# Team18_V1_3.net
KiCad netlist of a schematic drawn in EAGLE
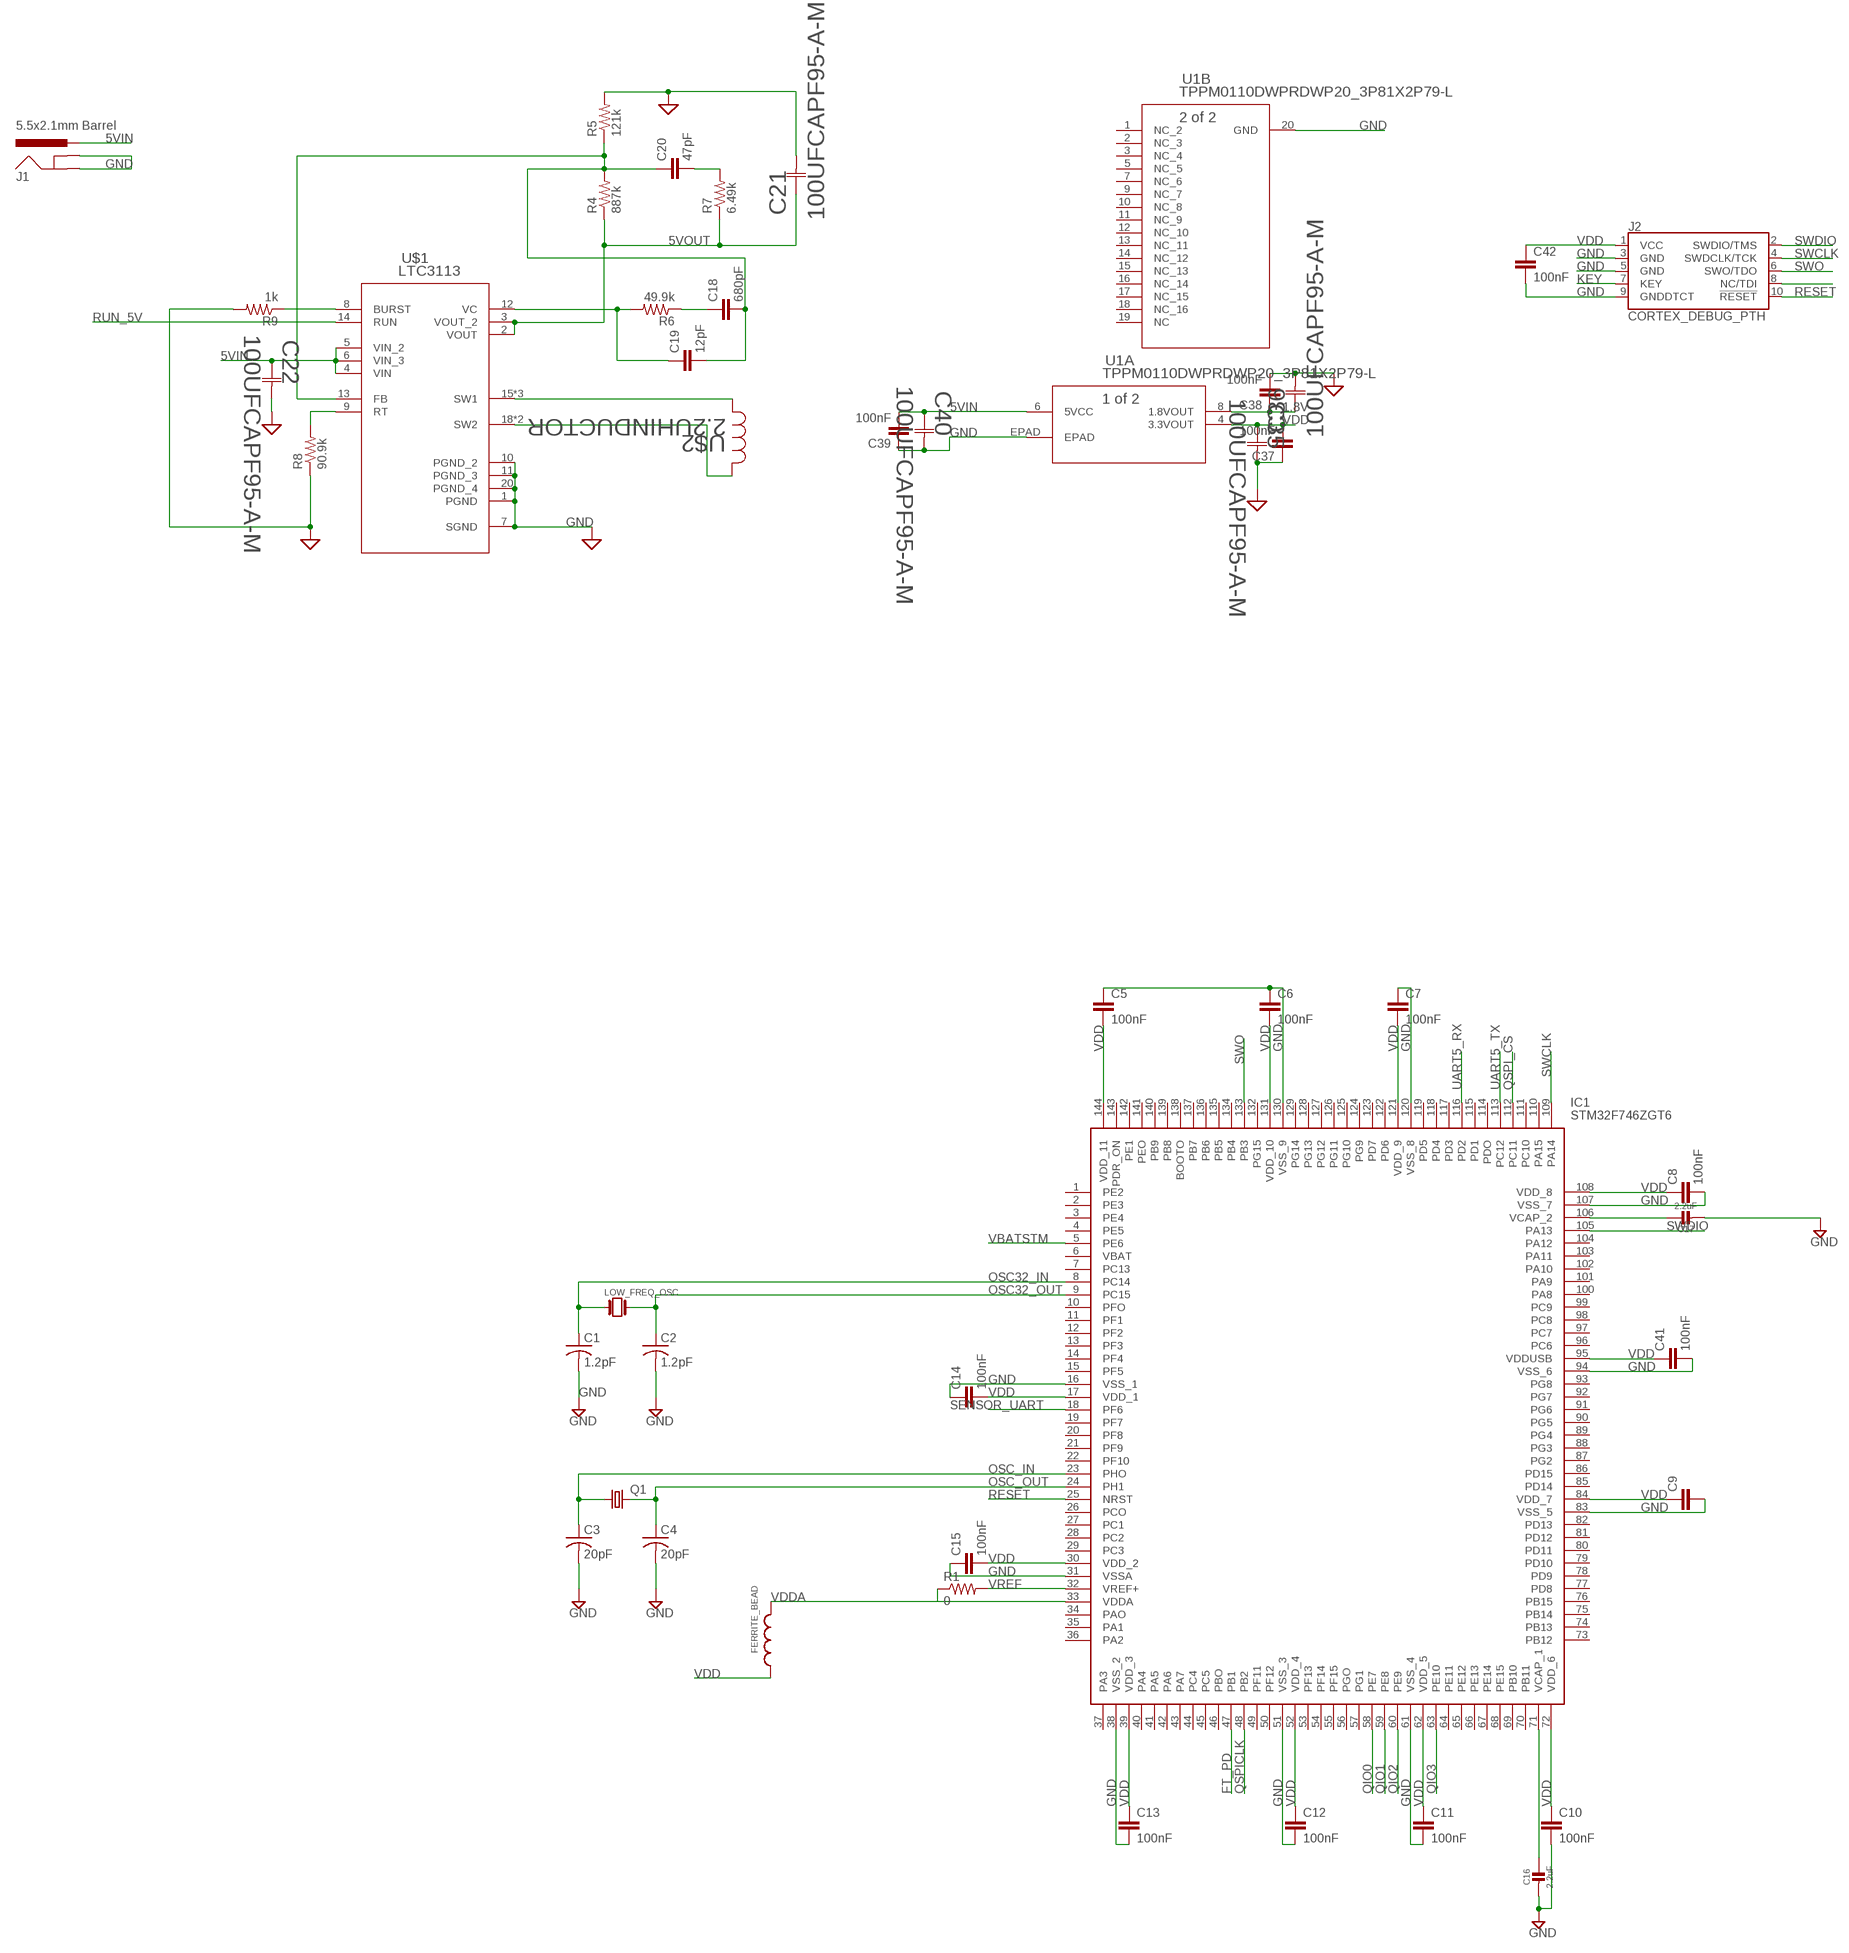
[diagram p0: schematic, sheet 1, part 1 of 2]
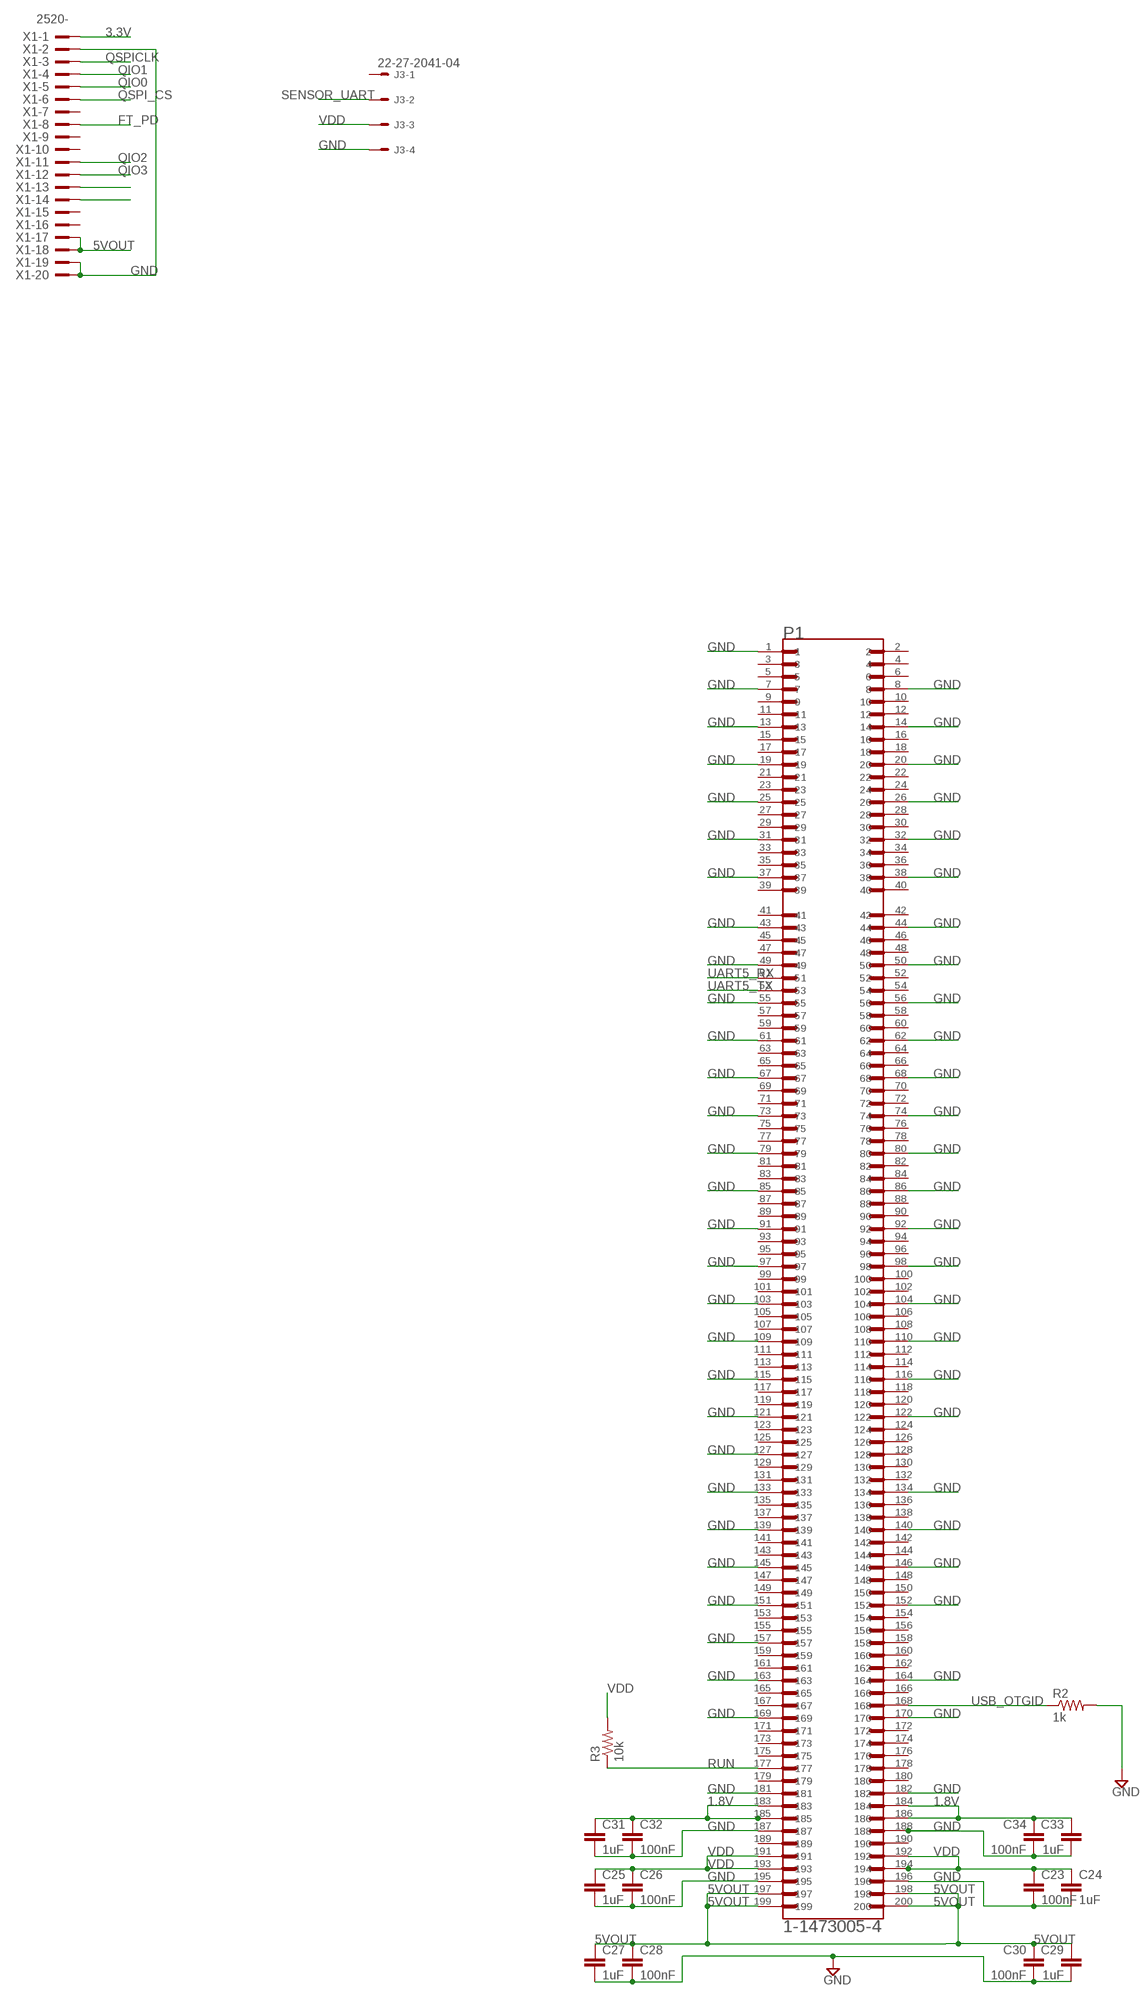
[diagram p1: schematic, sheet 1, part 2 of 2]

(export (version "E")
  (design (tool "Eeschema 10.0.6"))
  (components
    (comp (ref "C1")
      (value "1.2pF")
      (footprint "eagle-import:C0805")
      (libsource (lib "eagle-import") (part "C-USC0805"))
    )
    (comp (ref "C2")
      (value "1.2pF")
      (footprint "eagle-import:C0805")
      (libsource (lib "eagle-import") (part "C-USC0805"))
    )
    (comp (ref "C3")
      (value "20pF")
      (footprint "eagle-import:C0805")
      (libsource (lib "eagle-import") (part "C-USC0805"))
    )
    (comp (ref "C4")
      (value "20pF")
      (footprint "eagle-import:C0805")
      (libsource (lib "eagle-import") (part "C-USC0805"))
    )
    (comp (ref "C5")
      (value "100nF")
      (footprint "eagle-import:C0805")
      (libsource (lib "eagle-import") (part "C-EUC0805"))
    )
    (comp (ref "C6")
      (value "100nF")
      (footprint "eagle-import:C0805")
      (libsource (lib "eagle-import") (part "C-EUC0805"))
    )
    (comp (ref "C7")
      (value "100nF")
      (footprint "eagle-import:C0805")
      (libsource (lib "eagle-import") (part "C-EUC0805"))
    )
    (comp (ref "C8")
      (value "100nF")
      (footprint "eagle-import:C0805")
      (libsource (lib "eagle-import") (part "C-EUC0805"))
    )
    (comp (ref "C9")
      (value "C-EUC0805")
      (footprint "eagle-import:C0805")
      (libsource (lib "eagle-import") (part "C-EUC0805"))
    )
    (comp (ref "C10")
      (value "100nF")
      (footprint "eagle-import:C0805")
      (libsource (lib "eagle-import") (part "C-EUC0805"))
    )
    (comp (ref "C11")
      (value "100nF")
      (footprint "eagle-import:C0805")
      (libsource (lib "eagle-import") (part "C-EUC0805"))
    )
    (comp (ref "C12")
      (value "100nF")
      (footprint "eagle-import:C0805")
      (libsource (lib "eagle-import") (part "C-EUC0805"))
    )
    (comp (ref "C13")
      (value "100nF")
      (footprint "eagle-import:C0805")
      (libsource (lib "eagle-import") (part "C-EUC0805"))
    )
    (comp (ref "C14")
      (value "100nF")
      (footprint "eagle-import:C0805")
      (libsource (lib "eagle-import") (part "C-EUC0805"))
    )
    (comp (ref "C15")
      (value "100nF")
      (footprint "eagle-import:C0805")
      (libsource (lib "eagle-import") (part "C-EUC0805"))
    )
    (comp (ref "C16")
      (value "2.2uF")
      (footprint "eagle-import:0805-NO")
      (libsource (lib "eagle-import") (part "CAP_CERAMIC0805-NOOUTLINE"))
    )
    (comp (ref "C17")
      (value "2.2uF")
      (footprint "eagle-import:0805-NO")
      (libsource (lib "eagle-import") (part "CAP_CERAMIC0805-NOOUTLINE"))
    )
    (comp (ref "C18")
      (value "680pF")
      (footprint "eagle-import:C0805")
      (libsource (lib "eagle-import") (part "C-EUC0805"))
    )
    (comp (ref "C19")
      (value "12pF")
      (footprint "eagle-import:C0805")
      (libsource (lib "eagle-import") (part "C-EUC0805"))
    )
    (comp (ref "C20")
      (value "47pF")
      (footprint "eagle-import:C0805")
      (libsource (lib "eagle-import") (part "C-EUC0805"))
    )
    (comp (ref "C21")
      (value "100UFCAPF95-A-M")
      (footprint "eagle-import:F95-A-M")
      (fields (field (name "MANUFACTURER_PART_NUMBER") "F951A107KAAAQ2"))
      (libsource (lib "eagle-import") (part "100UFCAPF95-A-M"))
    )
    (comp (ref "C22")
      (value "100UFCAPF95-A-M")
      (footprint "eagle-import:F95-A-M")
      (fields (field (name "MANUFACTURER_PART_NUMBER") "F951A107KAAAQ2"))
      (libsource (lib "eagle-import") (part "100UFCAPF95-A-M"))
    )
    (comp (ref "C23")
      (value "100nF")
      (footprint "eagle-import:C0805")
      (libsource (lib "eagle-import") (part "C-EUC0805"))
    )
    (comp (ref "C24")
      (value "1uF")
      (footprint "eagle-import:C0805")
      (libsource (lib "eagle-import") (part "C-EUC0805"))
    )
    (comp (ref "C25")
      (value "1uF")
      (footprint "eagle-import:C0805")
      (libsource (lib "eagle-import") (part "C-EUC0805"))
    )
    (comp (ref "C26")
      (value "100nF")
      (footprint "eagle-import:C0805")
      (libsource (lib "eagle-import") (part "C-EUC0805"))
    )
    (comp (ref "C27")
      (value "1uF")
      (footprint "eagle-import:C0805")
      (libsource (lib "eagle-import") (part "C-EUC0805"))
    )
    (comp (ref "C28")
      (value "100nF")
      (footprint "eagle-import:C0805")
      (libsource (lib "eagle-import") (part "C-EUC0805"))
    )
    (comp (ref "C29")
      (value "1uF")
      (footprint "eagle-import:C0805")
      (libsource (lib "eagle-import") (part "C-EUC0805"))
    )
    (comp (ref "C30")
      (value "100nF")
      (footprint "eagle-import:C0805")
      (libsource (lib "eagle-import") (part "C-EUC0805"))
    )
    (comp (ref "C31")
      (value "1uF")
      (footprint "eagle-import:C0805")
      (libsource (lib "eagle-import") (part "C-EUC0805"))
    )
    (comp (ref "C32")
      (value "100nF")
      (footprint "eagle-import:C0805")
      (libsource (lib "eagle-import") (part "C-EUC0805"))
    )
    (comp (ref "C33")
      (value "1uF")
      (footprint "eagle-import:C0805")
      (libsource (lib "eagle-import") (part "C-EUC0805"))
    )
    (comp (ref "C34")
      (value "100nF")
      (footprint "eagle-import:C0805")
      (libsource (lib "eagle-import") (part "C-EUC0805"))
    )
    (comp (ref "C35")
      (value "100UFCAPF95-A-M")
      (footprint "eagle-import:F95-A-M")
      (fields (field (name "MANUFACTURER_PART_NUMBER") "F951A107KAAAQ2"))
      (libsource (lib "eagle-import") (part "100UFCAPF95-A-M"))
    )
    (comp (ref "C36")
      (value "100UFCAPF95-A-M")
      (footprint "eagle-import:F95-A-M")
      (fields (field (name "MANUFACTURER_PART_NUMBER") "F951A107KAAAQ2"))
      (libsource (lib "eagle-import") (part "100UFCAPF95-A-M"))
    )
    (comp (ref "C37")
      (value "100nF")
      (footprint "eagle-import:C0805")
      (libsource (lib "eagle-import") (part "C-EUC0805"))
    )
    (comp (ref "C38")
      (value "100nF")
      (footprint "eagle-import:C0805")
      (libsource (lib "eagle-import") (part "C-EUC0805"))
    )
    (comp (ref "C39")
      (value "100nF")
      (footprint "eagle-import:C0805")
      (libsource (lib "eagle-import") (part "C-EUC0805"))
    )
    (comp (ref "C40")
      (value "100UFCAPF95-A-M")
      (footprint "eagle-import:F95-A-M")
      (fields (field (name "MANUFACTURER_PART_NUMBER") "F951A107KAAAQ2"))
      (libsource (lib "eagle-import") (part "100UFCAPF95-A-M"))
    )
    (comp (ref "C41")
      (value "100nF")
      (footprint "eagle-import:C0805")
      (libsource (lib "eagle-import") (part "C-EUC0805"))
    )
    (comp (ref "C42")
      (value "100nF")
      (footprint "eagle-import:C0805")
      (libsource (lib "eagle-import") (part "C-EUC0805"))
    )
    (comp (ref "FERRITE_BEAD")
      (value "WE-CBA_0805_782853112_HC")
      (footprint "eagle-import:WE-CBA_0805(W=4)")
      (libsource (lib "eagle-import") (part "WE-CBA_0805_HC_782853112"))
    )
    (comp (ref "IC1")
      (value "STM32F746ZGT6")
      (footprint "eagle-import:QFP50P2200X2200X160-144N")
      (fields
        (field (name "MOUSER_PART_NUMBER") "511-STM32F746ZGT6")
        (field (name "RS_PART_NUMBER") "8820290")
      )
      (libsource (lib "eagle-import") (part "STM32F746ZGT6"))
    )
    (comp (ref "J1")
      (value "5.5x2.1mm Barrel")
      (footprint "eagle-import:POWER_JACK_SMD")
      (libsource (lib "eagle-import") (part "POWER_JACKSMD"))
    )
    (comp (ref "J2")
      (value "CORTEX_DEBUG_PTH")
      (footprint "eagle-import:2X5-PTH-1.27MM")
      (libsource (lib "eagle-import") (part "CORTEX_DEBUG_PTH"))
    )
    (comp (ref "J3")
      (value "22-27-2041-04")
      (footprint "eagle-import:6410-04")
      (fields (field (name "MF") "MOLEX"))
      (libsource (lib "eagle-import") (part "22-?-0427-2041"))
    )
    (comp (ref "LOW_FREQ_OSC")
      (value "GENERIC-CRYSTAL_FC135")
      (footprint "eagle-import:FC135")
      (libsource (lib "eagle-import") (part "GENERIC-CRYSTAL_FC135"))
    )
    (comp (ref "P1")
      (value "1-1473005-4")
      (footprint "eagle-import:TE_1-1473005-4")
      (fields (field (name "MF") "TE Connectivity"))
      (libsource (lib "eagle-import") (part "1-1473005-4"))
    )
    (comp (ref "Q1")
      (value "CRYSTALHC49UP")
      (footprint "eagle-import:HC49UP")
      (libsource (lib "eagle-import") (part "CRYSTALHC49UP"))
    )
    (comp (ref "R1")
      (value "0")
      (footprint "eagle-import:R0805")
      (libsource (lib "eagle-import") (part "R-US_R0805"))
    )
    (comp (ref "R2")
      (value "1k")
      (footprint "eagle-import:R0805")
      (libsource (lib "eagle-import") (part "R-US_R0805"))
    )
    (comp (ref "R3")
      (value "10k")
      (footprint "eagle-import:R0805")
      (libsource (lib "eagle-import") (part "R-US_R0805"))
    )
    (comp (ref "R4")
      (value "887k")
      (footprint "eagle-import:R0805")
      (libsource (lib "eagle-import") (part "resistor_348_R-US_R0805"))
    )
    (comp (ref "R5")
      (value "121k")
      (footprint "eagle-import:R0805")
      (libsource (lib "eagle-import") (part "resistor_348_R-US_R0805"))
    )
    (comp (ref "R6")
      (value "49.9k")
      (footprint "eagle-import:R0805")
      (libsource (lib "eagle-import") (part "resistor_348_R-US_R0805"))
    )
    (comp (ref "R7")
      (value "6.49k")
      (footprint "eagle-import:R0805")
      (libsource (lib "eagle-import") (part "resistor_348_R-US_R0805"))
    )
    (comp (ref "R8")
      (value "90.9k")
      (footprint "eagle-import:R0805")
      (libsource (lib "eagle-import") (part "resistor_348_R-US_R0805"))
    )
    (comp (ref "R9")
      (value "1k")
      (footprint "eagle-import:R0805")
      (libsource (lib "eagle-import") (part "resistor_348_R-US_R0805"))
    )
    (comp (ref "U$1")
      (value "LTC3113")
      (footprint "eagle-import:TSSOP-20_FE_CA")
      (libsource (lib "eagle-import") (part "LTC3113"))
    )
    (comp (ref "U$2")
      (value "2.2UHINDUCTOR")
      (footprint "eagle-import:IND_10040")
      (libsource (lib "eagle-import") (part "2.2UHINDUCTOR"))
    )
    (comp (ref "U1")
      (value "TPPM0110DWPRDWP20_3P81X2P79-L")
      (footprint "eagle-import:DWP20_3P81X2P79-L")
      (fields (field (name "MANUFACTURER_PART_NUMBER") "TPPM0110DWPR"))
      (libsource (lib "eagle-import") (part "TPPM0110DWPRDWP20_3P81X2P79-L"))
    )
    (comp (ref "X1")
      (value "2520-")
      (footprint "eagle-import:PAK100_2500-20")
      (libsource (lib "eagle-import") (part "2520-"))
    )
  )
  (nets
    (net (code "1") (name "/1.8V") (class "Default")
      (node (ref "C31") (pin "1") (pinfunction "1_1") (pintype "passive"))
      (node (ref "C32") (pin "1") (pinfunction "1_1") (pintype "passive"))
      (node (ref "C33") (pin "1") (pinfunction "1_1") (pintype "passive"))
      (node (ref "C34") (pin "1") (pinfunction "1_1") (pintype "passive"))
      (node (ref "C36") (pin "1") (pinfunction "1_1") (pintype "passive"))
      (node (ref "C38") (pin "1") (pinfunction "1_1") (pintype "passive"))
      (node (ref "P1") (pin "183") (pinfunction "183_183") (pintype "passive"))
      (node (ref "P1") (pin "184") (pinfunction "184_184") (pintype "passive"))
      (node (ref "P1") (pin "185") (pinfunction "185_185") (pintype "passive"))
      (node (ref "P1") (pin "186") (pinfunction "186_186") (pintype "passive"))
      (node (ref "U1") (pin "8") (pinfunction "1.8VOUT_8") (pintype "output"))
    )
    (net (code "2") (name "/3.3V") (class "Default")
      (node (ref "X1") (pin "1") (pinfunction "KL_1") (pintype "passive"))
    )
    (net (code "3") (name "/5VIN") (class "Default")
      (node (ref "C22") (pin "1") (pinfunction "1_1") (pintype "passive"))
      (node (ref "C39") (pin "2") (pinfunction "2_2") (pintype "passive"))
      (node (ref "C40") (pin "1") (pinfunction "1_1") (pintype "passive"))
      (node (ref "J1") (pin "VIN0") (pinfunction "PWR_VIN0") (pintype "bidirectional"))
      (node (ref "U$1") (pin "4") (pinfunction "VIN_4") (pintype "passive"))
      (node (ref "U$1") (pin "5") (pinfunction "VIN_2_5") (pintype "passive"))
      (node (ref "U$1") (pin "6") (pinfunction "VIN_3_6") (pintype "passive"))
      (node (ref "U1") (pin "6") (pinfunction "5VCC_6") (pintype "input"))
    )
    (net (code "4") (name "/5VOUT") (class "Default")
      (node (ref "C21") (pin "1") (pinfunction "1_1") (pintype "passive"))
      (node (ref "C27") (pin "1") (pinfunction "1_1") (pintype "passive"))
      (node (ref "C28") (pin "1") (pinfunction "1_1") (pintype "passive"))
      (node (ref "C29") (pin "1") (pinfunction "1_1") (pintype "passive"))
      (node (ref "C30") (pin "1") (pinfunction "1_1") (pintype "passive"))
      (node (ref "P1") (pin "197") (pinfunction "197_197") (pintype "passive"))
      (node (ref "P1") (pin "198") (pinfunction "198_198") (pintype "passive"))
      (node (ref "P1") (pin "199") (pinfunction "199_199") (pintype "passive"))
      (node (ref "P1") (pin "200") (pinfunction "200_200") (pintype "passive"))
      (node (ref "R4") (pin "1") (pinfunction "1_1") (pintype "passive"))
      (node (ref "R7") (pin "1") (pinfunction "1_1") (pintype "passive"))
      (node (ref "U$1") (pin "2") (pinfunction "VOUT_2") (pintype "passive"))
      (node (ref "U$1") (pin "3") (pinfunction "VOUT_2_3") (pintype "passive"))
      (node (ref "X1") (pin "17") (pinfunction "KL_17") (pintype "passive"))
      (node (ref "X1") (pin "18") (pinfunction "KL_18") (pintype "passive"))
    )
    (net (code "5") (name "/FT_PD") (class "Default")
      (node (ref "IC1") (pin "47") (pinfunction "PB1_47") (pintype "bidirectional"))
      (node (ref "X1") (pin "8") (pinfunction "KL_8") (pintype "passive"))
    )
    (net (code "6") (name "/KEY") (class "Default")
      (node (ref "J2") (pin "7") (pinfunction "KEY_7") (pintype "bidirectional"))
    )
    (net (code "7") (name "/OSC32_IN") (class "Default")
      (node (ref "C1") (pin "1") (pinfunction "1_1") (pintype "passive"))
      (node (ref "IC1") (pin "8") (pinfunction "PC14_8") (pintype "bidirectional"))
      (node (ref "LOW_FREQ_OSC") (pin "X1") (pinfunction "1_X1") (pintype "passive"))
    )
    (net (code "8") (name "/OSC32_OUT") (class "Default")
      (node (ref "C2") (pin "1") (pinfunction "1_1") (pintype "passive"))
      (node (ref "IC1") (pin "9") (pinfunction "PC15_9") (pintype "bidirectional"))
      (node (ref "LOW_FREQ_OSC") (pin "X2") (pinfunction "2_X2") (pintype "passive"))
    )
    (net (code "9") (name "/OSC_IN") (class "Default")
      (node (ref "C3") (pin "1") (pinfunction "1_1") (pintype "passive"))
      (node (ref "IC1") (pin "23") (pinfunction "PHO_23") (pintype "bidirectional"))
      (node (ref "Q1") (pin "1") (pinfunction "1_1") (pintype "passive"))
    )
    (net (code "10") (name "/OSC_OUT") (class "Default")
      (node (ref "C4") (pin "1") (pinfunction "1_1") (pintype "passive"))
      (node (ref "IC1") (pin "24") (pinfunction "PH1_24") (pintype "bidirectional"))
      (node (ref "Q1") (pin "2") (pinfunction "2_2") (pintype "passive"))
    )
    (net (code "11") (name "/QIO0") (class "Default")
      (node (ref "IC1") (pin "58") (pinfunction "PE7_58") (pintype "bidirectional"))
      (node (ref "X1") (pin "5") (pinfunction "KL_5") (pintype "passive"))
    )
    (net (code "12") (name "/QIO1") (class "Default")
      (node (ref "IC1") (pin "59") (pinfunction "PE8_59") (pintype "bidirectional"))
      (node (ref "X1") (pin "4") (pinfunction "KL_4") (pintype "passive"))
    )
    (net (code "13") (name "/QIO2") (class "Default")
      (node (ref "IC1") (pin "60") (pinfunction "PE9_60") (pintype "bidirectional"))
      (node (ref "X1") (pin "11") (pinfunction "KL_11") (pintype "passive"))
    )
    (net (code "14") (name "/QIO3") (class "Default")
      (node (ref "IC1") (pin "63") (pinfunction "PE10_63") (pintype "bidirectional"))
      (node (ref "X1") (pin "12") (pinfunction "KL_12") (pintype "passive"))
    )
    (net (code "15") (name "/QSPICLK") (class "Default")
      (node (ref "IC1") (pin "48") (pinfunction "PB2_48") (pintype "bidirectional"))
      (node (ref "X1") (pin "3") (pinfunction "KL_3") (pintype "passive"))
    )
    (net (code "16") (name "/QSPI_CS") (class "Default")
      (node (ref "IC1") (pin "112") (pinfunction "PC11_112") (pintype "bidirectional"))
      (node (ref "X1") (pin "6") (pinfunction "KL_6") (pintype "passive"))
    )
    (net (code "17") (name "/RESET") (class "Default")
      (node (ref "IC1") (pin "25") (pinfunction "NRST_25") (pintype "input"))
      (node (ref "J2") (pin "10") (pinfunction "~{RESET}_10") (pintype "bidirectional"))
    )
    (net (code "18") (name "/RUN") (class "Default")
      (node (ref "P1") (pin "177") (pinfunction "177_177") (pintype "passive"))
      (node (ref "R3") (pin "1") (pinfunction "1_1") (pintype "passive"))
    )
    (net (code "19") (name "/RUN_5V") (class "Default")
      (node (ref "U$1") (pin "14") (pinfunction "RUN_14") (pintype "passive"))
    )
    (net (code "20") (name "/SENSOR_UART") (class "Default")
      (node (ref "IC1") (pin "18") (pinfunction "PF6_18") (pintype "bidirectional"))
      (node (ref "J3") (pin "2") (pinfunction "S_2") (pintype "passive"))
    )
    (net (code "21") (name "/SWCLK") (class "Default")
      (node (ref "IC1") (pin "109") (pinfunction "PA14_109") (pintype "bidirectional"))
      (node (ref "J2") (pin "4") (pinfunction "SWDCLK/TCK_4") (pintype "bidirectional"))
    )
    (net (code "22") (name "/SWDIO") (class "Default")
      (node (ref "IC1") (pin "105") (pinfunction "PA13_105") (pintype "bidirectional"))
      (node (ref "J2") (pin "2") (pinfunction "SWDIO/TMS_2") (pintype "bidirectional"))
    )
    (net (code "23") (name "/SWO") (class "Default")
      (node (ref "IC1") (pin "133") (pinfunction "PB3_133") (pintype "bidirectional"))
      (node (ref "J2") (pin "6") (pinfunction "SWO/TDO_6") (pintype "bidirectional"))
    )
    (net (code "24") (name "/UART5_RX") (class "Default")
      (node (ref "IC1") (pin "116") (pinfunction "PD2_116") (pintype "bidirectional"))
      (node (ref "P1") (pin "51") (pinfunction "51_51") (pintype "passive"))
    )
    (net (code "25") (name "/UART5_TX") (class "Default")
      (node (ref "IC1") (pin "113") (pinfunction "PC12_113") (pintype "bidirectional"))
      (node (ref "P1") (pin "53") (pinfunction "53_53") (pintype "passive"))
    )
    (net (code "26") (name "/USB_OTGID") (class "Default")
      (node (ref "P1") (pin "168") (pinfunction "168_168") (pintype "passive"))
      (node (ref "R2") (pin "1") (pinfunction "1_1") (pintype "passive"))
    )
    (net (code "27") (name "/VBATSTM") (class "Default")
      (node (ref "IC1") (pin "5") (pinfunction "PE6_5") (pintype "bidirectional"))
    )
    (net (code "28") (name "/VDD") (class "Default")
      (node (ref "C10") (pin "1") (pinfunction "1_1") (pintype "passive"))
      (node (ref "C11") (pin "1") (pinfunction "1_1") (pintype "passive"))
      (node (ref "C12") (pin "1") (pinfunction "1_1") (pintype "passive"))
      (node (ref "C13") (pin "1") (pinfunction "1_1") (pintype "passive"))
      (node (ref "C14") (pin "2") (pinfunction "2_2") (pintype "passive"))
      (node (ref "C15") (pin "2") (pinfunction "2_2") (pintype "passive"))
      (node (ref "C23") (pin "1") (pinfunction "1_1") (pintype "passive"))
      (node (ref "C24") (pin "1") (pinfunction "1_1") (pintype "passive"))
      (node (ref "C25") (pin "1") (pinfunction "1_1") (pintype "passive"))
      (node (ref "C26") (pin "1") (pinfunction "1_1") (pintype "passive"))
      (node (ref "C35") (pin "1") (pinfunction "1_1") (pintype "passive"))
      (node (ref "C37") (pin "2") (pinfunction "2_2") (pintype "passive"))
      (node (ref "C41") (pin "1") (pinfunction "1_1") (pintype "passive"))
      (node (ref "C42") (pin "1") (pinfunction "1_1") (pintype "passive"))
      (node (ref "C5") (pin "2") (pinfunction "2_2") (pintype "passive"))
      (node (ref "C6") (pin "2") (pinfunction "2_2") (pintype "passive"))
      (node (ref "C7") (pin "2") (pinfunction "2_2") (pintype "passive"))
      (node (ref "C8") (pin "1") (pinfunction "1_1") (pintype "passive"))
      (node (ref "C9") (pin "1") (pinfunction "1_1") (pintype "passive"))
      (node (ref "FERRITE_BEAD") (pin "1") (pinfunction "1_1") (pintype "passive"))
      (node (ref "IC1") (pin "108") (pinfunction "VDD_8_108") (pintype "power_in"))
      (node (ref "IC1") (pin "121") (pinfunction "VDD_9_121") (pintype "power_in"))
      (node (ref "IC1") (pin "131") (pinfunction "VDD_10_131") (pintype "power_in"))
      (node (ref "IC1") (pin "144") (pinfunction "VDD_11_144") (pintype "power_in"))
      (node (ref "IC1") (pin "17") (pinfunction "VDD_1_17") (pintype "power_in"))
      (node (ref "IC1") (pin "30") (pinfunction "VDD_2_30") (pintype "power_in"))
      (node (ref "IC1") (pin "39") (pinfunction "VDD_3_39") (pintype "power_in"))
      (node (ref "IC1") (pin "52") (pinfunction "VDD_4_52") (pintype "power_in"))
      (node (ref "IC1") (pin "62") (pinfunction "VDD_5_62") (pintype "power_in"))
      (node (ref "IC1") (pin "72") (pinfunction "VDD_6_72") (pintype "power_in"))
      (node (ref "IC1") (pin "84") (pinfunction "VDD_7_84") (pintype "power_in"))
      (node (ref "IC1") (pin "95") (pinfunction "VDDUSB_95") (pintype "power_in"))
      (node (ref "J2") (pin "1") (pinfunction "VCC_1") (pintype "bidirectional"))
      (node (ref "J3") (pin "3") (pinfunction "S_3") (pintype "passive"))
      (node (ref "P1") (pin "191") (pinfunction "191_191") (pintype "passive"))
      (node (ref "P1") (pin "192") (pinfunction "192_192") (pintype "passive"))
      (node (ref "P1") (pin "193") (pinfunction "193_193") (pintype "passive"))
      (node (ref "P1") (pin "194") (pinfunction "194_194") (pintype "passive"))
      (node (ref "R3") (pin "2") (pinfunction "2_2") (pintype "passive"))
      (node (ref "U1") (pin "4") (pinfunction "3.3VOUT_4") (pintype "output"))
    )
    (net (code "29") (name "/VDDA") (class "Default")
      (node (ref "FERRITE_BEAD") (pin "2") (pinfunction "2_2") (pintype "passive"))
      (node (ref "IC1") (pin "33") (pinfunction "VDDA_33") (pintype "power_in"))
      (node (ref "R1") (pin "1") (pinfunction "1_1") (pintype "passive"))
    )
    (net (code "30") (name "/VREF") (class "Default")
      (node (ref "IC1") (pin "32") (pinfunction "VREF+_32") (pintype "input"))
      (node (ref "R1") (pin "2") (pinfunction "2_2") (pintype "passive"))
    )
    (net (code "31") (name "GND") (class "Default")
      (node (ref "C1") (pin "2") (pinfunction "2_2") (pintype "passive"))
      (node (ref "C10") (pin "2") (pinfunction "2_2") (pintype "passive"))
      (node (ref "C11") (pin "2") (pinfunction "2_2") (pintype "passive"))
      (node (ref "C12") (pin "2") (pinfunction "2_2") (pintype "passive"))
      (node (ref "C13") (pin "2") (pinfunction "2_2") (pintype "passive"))
      (node (ref "C14") (pin "1") (pinfunction "1_1") (pintype "passive"))
      (node (ref "C15") (pin "1") (pinfunction "1_1") (pintype "passive"))
      (node (ref "C16") (pin "2") (pinfunction "2_2") (pintype "passive"))
      (node (ref "C17") (pin "2") (pinfunction "2_2") (pintype "passive"))
      (node (ref "C2") (pin "2") (pinfunction "2_2") (pintype "passive"))
      (node (ref "C21") (pin "2") (pinfunction "2_2") (pintype "passive"))
      (node (ref "C22") (pin "2") (pinfunction "2_2") (pintype "passive"))
      (node (ref "C23") (pin "2") (pinfunction "2_2") (pintype "passive"))
      (node (ref "C24") (pin "2") (pinfunction "2_2") (pintype "passive"))
      (node (ref "C25") (pin "2") (pinfunction "2_2") (pintype "passive"))
      (node (ref "C26") (pin "2") (pinfunction "2_2") (pintype "passive"))
      (node (ref "C27") (pin "2") (pinfunction "2_2") (pintype "passive"))
      (node (ref "C28") (pin "2") (pinfunction "2_2") (pintype "passive"))
      (node (ref "C29") (pin "2") (pinfunction "2_2") (pintype "passive"))
      (node (ref "C3") (pin "2") (pinfunction "2_2") (pintype "passive"))
      (node (ref "C30") (pin "2") (pinfunction "2_2") (pintype "passive"))
      (node (ref "C31") (pin "2") (pinfunction "2_2") (pintype "passive"))
      (node (ref "C32") (pin "2") (pinfunction "2_2") (pintype "passive"))
      (node (ref "C33") (pin "2") (pinfunction "2_2") (pintype "passive"))
      (node (ref "C34") (pin "2") (pinfunction "2_2") (pintype "passive"))
      (node (ref "C35") (pin "2") (pinfunction "2_2") (pintype "passive"))
      (node (ref "C36") (pin "2") (pinfunction "2_2") (pintype "passive"))
      (node (ref "C37") (pin "1") (pinfunction "1_1") (pintype "passive"))
      (node (ref "C38") (pin "2") (pinfunction "2_2") (pintype "passive"))
      (node (ref "C39") (pin "1") (pinfunction "1_1") (pintype "passive"))
      (node (ref "C4") (pin "2") (pinfunction "2_2") (pintype "passive"))
      (node (ref "C40") (pin "2") (pinfunction "2_2") (pintype "passive"))
      (node (ref "C41") (pin "2") (pinfunction "2_2") (pintype "passive"))
      (node (ref "C42") (pin "2") (pinfunction "2_2") (pintype "passive"))
      (node (ref "C5") (pin "1") (pinfunction "1_1") (pintype "passive"))
      (node (ref "C6") (pin "1") (pinfunction "1_1") (pintype "passive"))
      (node (ref "C7") (pin "1") (pinfunction "1_1") (pintype "passive"))
      (node (ref "C8") (pin "2") (pinfunction "2_2") (pintype "passive"))
      (node (ref "C9") (pin "2") (pinfunction "2_2") (pintype "passive"))
      (node (ref "IC1") (pin "107") (pinfunction "VSS_7_107") (pintype "power_in"))
      (node (ref "IC1") (pin "120") (pinfunction "VSS_8_120") (pintype "power_in"))
      (node (ref "IC1") (pin "130") (pinfunction "VSS_9_130") (pintype "power_in"))
      (node (ref "IC1") (pin "16") (pinfunction "VSS_1_16") (pintype "power_in"))
      (node (ref "IC1") (pin "31") (pinfunction "VSSA_31") (pintype "power_in"))
      (node (ref "IC1") (pin "38") (pinfunction "VSS_2_38") (pintype "power_in"))
      (node (ref "IC1") (pin "51") (pinfunction "VSS_3_51") (pintype "power_in"))
      (node (ref "IC1") (pin "61") (pinfunction "VSS_4_61") (pintype "power_in"))
      (node (ref "IC1") (pin "83") (pinfunction "VSS_5_83") (pintype "power_in"))
      (node (ref "IC1") (pin "94") (pinfunction "VSS_6_94") (pintype "power_in"))
      (node (ref "J1") (pin "GND") (pinfunction "GNDBREAK_GND") (pintype "bidirectional"))
      (node (ref "J1") (pin "P$4") (pinfunction "GND_P$4") (pintype "bidirectional"))
      (node (ref "J2") (pin "3") (pinfunction "GND_3") (pintype "bidirectional"))
      (node (ref "J2") (pin "5") (pinfunction "GND_5") (pintype "bidirectional"))
      (node (ref "J2") (pin "9") (pinfunction "GNDDTCT_9") (pintype "bidirectional"))
      (node (ref "J3") (pin "4") (pinfunction "S_4") (pintype "passive"))
      (node (ref "P1") (pin "1") (pinfunction "1_1") (pintype "passive"))
      (node (ref "P1") (pin "103") (pinfunction "103_103") (pintype "passive"))
      (node (ref "P1") (pin "104") (pinfunction "104_104") (pintype "passive"))
      (node (ref "P1") (pin "109") (pinfunction "109_109") (pintype "passive"))
      (node (ref "P1") (pin "110") (pinfunction "110_110") (pintype "passive"))
      (node (ref "P1") (pin "115") (pinfunction "115_115") (pintype "passive"))
      (node (ref "P1") (pin "116") (pinfunction "116_116") (pintype "passive"))
      (node (ref "P1") (pin "121") (pinfunction "121_121") (pintype "passive"))
      (node (ref "P1") (pin "122") (pinfunction "122_122") (pintype "passive"))
      (node (ref "P1") (pin "127") (pinfunction "127_127") (pintype "passive"))
      (node (ref "P1") (pin "13") (pinfunction "13_13") (pintype "passive"))
      (node (ref "P1") (pin "133") (pinfunction "133_133") (pintype "passive"))
      (node (ref "P1") (pin "134") (pinfunction "134_134") (pintype "passive"))
      (node (ref "P1") (pin "139") (pinfunction "139_139") (pintype "passive"))
      (node (ref "P1") (pin "14") (pinfunction "14_14") (pintype "passive"))
      (node (ref "P1") (pin "140") (pinfunction "140_140") (pintype "passive"))
      (node (ref "P1") (pin "145") (pinfunction "145_145") (pintype "passive"))
      (node (ref "P1") (pin "146") (pinfunction "146_146") (pintype "passive"))
      (node (ref "P1") (pin "151") (pinfunction "151_151") (pintype "passive"))
      (node (ref "P1") (pin "152") (pinfunction "152_152") (pintype "passive"))
      (node (ref "P1") (pin "157") (pinfunction "157_157") (pintype "passive"))
      (node (ref "P1") (pin "163") (pinfunction "163_163") (pintype "passive"))
      (node (ref "P1") (pin "164") (pinfunction "164_164") (pintype "passive"))
      (node (ref "P1") (pin "169") (pinfunction "169_169") (pintype "passive"))
      (node (ref "P1") (pin "170") (pinfunction "170_170") (pintype "passive"))
      (node (ref "P1") (pin "181") (pinfunction "181_181") (pintype "passive"))
      (node (ref "P1") (pin "182") (pinfunction "182_182") (pintype "passive"))
      (node (ref "P1") (pin "187") (pinfunction "187_187") (pintype "passive"))
      (node (ref "P1") (pin "188") (pinfunction "188_188") (pintype "passive"))
      (node (ref "P1") (pin "19") (pinfunction "19_19") (pintype "passive"))
      (node (ref "P1") (pin "195") (pinfunction "195_195") (pintype "passive"))
      (node (ref "P1") (pin "196") (pinfunction "196_196") (pintype "passive"))
      (node (ref "P1") (pin "20") (pinfunction "20_20") (pintype "passive"))
      (node (ref "P1") (pin "25") (pinfunction "25_25") (pintype "passive"))
      (node (ref "P1") (pin "26") (pinfunction "26_26") (pintype "passive"))
      (node (ref "P1") (pin "31") (pinfunction "31_31") (pintype "passive"))
      (node (ref "P1") (pin "32") (pinfunction "32_32") (pintype "passive"))
      (node (ref "P1") (pin "37") (pinfunction "37_37") (pintype "passive"))
      (node (ref "P1") (pin "38") (pinfunction "38_38") (pintype "passive"))
      (node (ref "P1") (pin "43") (pinfunction "43_43") (pintype "passive"))
      (node (ref "P1") (pin "44") (pinfunction "44_44") (pintype "passive"))
      (node (ref "P1") (pin "49") (pinfunction "49_49") (pintype "passive"))
      (node (ref "P1") (pin "50") (pinfunction "50_50") (pintype "passive"))
      (node (ref "P1") (pin "55") (pinfunction "55_55") (pintype "passive"))
      (node (ref "P1") (pin "56") (pinfunction "56_56") (pintype "passive"))
      (node (ref "P1") (pin "61") (pinfunction "61_61") (pintype "passive"))
      (node (ref "P1") (pin "62") (pinfunction "62_62") (pintype "passive"))
      (node (ref "P1") (pin "67") (pinfunction "67_67") (pintype "passive"))
      (node (ref "P1") (pin "68") (pinfunction "68_68") (pintype "passive"))
      (node (ref "P1") (pin "7") (pinfunction "7_7") (pintype "passive"))
      (node (ref "P1") (pin "73") (pinfunction "73_73") (pintype "passive"))
      (node (ref "P1") (pin "74") (pinfunction "74_74") (pintype "passive"))
      (node (ref "P1") (pin "79") (pinfunction "79_79") (pintype "passive"))
      (node (ref "P1") (pin "8") (pinfunction "8_8") (pintype "passive"))
      (node (ref "P1") (pin "80") (pinfunction "80_80") (pintype "passive"))
      (node (ref "P1") (pin "85") (pinfunction "85_85") (pintype "passive"))
      (node (ref "P1") (pin "86") (pinfunction "86_86") (pintype "passive"))
      (node (ref "P1") (pin "91") (pinfunction "91_91") (pintype "passive"))
      (node (ref "P1") (pin "92") (pinfunction "92_92") (pintype "passive"))
      (node (ref "P1") (pin "97") (pinfunction "97_97") (pintype "passive"))
      (node (ref "P1") (pin "98") (pinfunction "98_98") (pintype "passive"))
      (node (ref "R2") (pin "2") (pinfunction "2_2") (pintype "passive"))
      (node (ref "R5") (pin "2") (pinfunction "2_2") (pintype "passive"))
      (node (ref "R8") (pin "1") (pinfunction "1_1") (pintype "passive"))
      (node (ref "R9") (pin "2") (pinfunction "2_2") (pintype "passive"))
      (node (ref "U$1") (pin "1") (pinfunction "PGND_1") (pintype "passive"))
      (node (ref "U$1") (pin "10") (pinfunction "PGND_2_10") (pintype "passive"))
      (node (ref "U$1") (pin "11") (pinfunction "PGND_3_11") (pintype "passive"))
      (node (ref "U$1") (pin "20") (pinfunction "PGND_4_20") (pintype "passive"))
      (node (ref "U$1") (pin "7") (pinfunction "SGND_7") (pintype "passive"))
      (node (ref "U1") (pin "20") (pinfunction "GND_20") (pintype "power_in"))
      (node (ref "U1") (pin "EPAD") (pinfunction "EPAD_EPAD") (pintype "passive"))
      (node (ref "X1") (pin "19") (pinfunction "KL_19") (pintype "passive"))
      (node (ref "X1") (pin "2") (pinfunction "KL_2") (pintype "passive"))
      (node (ref "X1") (pin "20") (pinfunction "KL_20") (pintype "passive"))
    )
    (net (code "32") (name "Net-(C18-Pad1)") (class "Default")
      (node (ref "C18") (pin "1") (pinfunction "1_1") (pintype "passive"))
      (node (ref "R6") (pin "1") (pinfunction "1_1") (pintype "passive"))
    )
    (net (code "33") (name "Net-(C20-Pad2)") (class "Default")
      (node (ref "C20") (pin "2") (pinfunction "2_2") (pintype "passive"))
      (node (ref "R7") (pin "2") (pinfunction "2_2") (pintype "passive"))
    )
    (net (code "34") (name "Net-(IC1-VCAP_1)") (class "Default")
      (node (ref "C16") (pin "1") (pinfunction "1_1") (pintype "passive"))
      (node (ref "IC1") (pin "71") (pinfunction "VCAP_1_71") (pintype "bidirectional"))
    )
    (net (code "35") (name "Net-(IC1-VCAP_2)") (class "Default")
      (node (ref "C17") (pin "1") (pinfunction "1_1") (pintype "passive"))
      (node (ref "IC1") (pin "106") (pinfunction "VCAP_2_106") (pintype "bidirectional"))
    )
    (net (code "36") (name "Net-(U$1-BURST)") (class "Default")
      (node (ref "R9") (pin "1") (pinfunction "1_1") (pintype "passive"))
      (node (ref "U$1") (pin "8") (pinfunction "BURST_8") (pintype "passive"))
    )
    (net (code "37") (name "Net-(U$1-FB)") (class "Default")
      (node (ref "C18") (pin "2") (pinfunction "2_2") (pintype "passive"))
      (node (ref "C19") (pin "2") (pinfunction "2_2") (pintype "passive"))
      (node (ref "C20") (pin "1") (pinfunction "1_1") (pintype "passive"))
      (node (ref "R4") (pin "2") (pinfunction "2_2") (pintype "passive"))
      (node (ref "R5") (pin "1") (pinfunction "1_1") (pintype "passive"))
      (node (ref "U$1") (pin "13") (pinfunction "FB_13") (pintype "passive"))
    )
    (net (code "38") (name "Net-(U$1-RT)") (class "Default")
      (node (ref "R8") (pin "2") (pinfunction "2_2") (pintype "passive"))
      (node (ref "U$1") (pin "9") (pinfunction "RT_9") (pintype "passive"))
    )
    (net (code "39") (name "Net-(U$1-SW1-Pad15)") (class "Default")
      (node (ref "U$1") (pin "15") (pinfunction "SW1_15") (pintype "passive"))
      (node (ref "U$1") (pin "16") (pinfunction "SW1_16") (pintype "passive"))
      (node (ref "U$1") (pin "17") (pinfunction "SW1_17") (pintype "passive"))
      (node (ref "U$2") (pin "2") (pinfunction "2_2") (pintype "passive"))
    )
    (net (code "40") (name "Net-(U$1-SW2-Pad18)") (class "Default")
      (node (ref "U$1") (pin "18") (pinfunction "SW2_18") (pintype "passive"))
      (node (ref "U$1") (pin "19") (pinfunction "SW2_19") (pintype "passive"))
      (node (ref "U$2") (pin "1") (pinfunction "1_1") (pintype "passive"))
    )
    (net (code "41") (name "Net-(U$1-VC)") (class "Default")
      (node (ref "C19") (pin "1") (pinfunction "1_1") (pintype "passive"))
      (node (ref "R6") (pin "2") (pinfunction "2_2") (pintype "passive"))
      (node (ref "U$1") (pin "12") (pinfunction "VC_12") (pintype "passive"))
    )
    (net (code "42") (name "unconnected-(IC1-BOOTO-Pad138)") (class "Default")
      (node (ref "IC1") (pin "138") (pinfunction "BOOTO_138") (pintype "bidirectional"))
    )
    (net (code "43") (name "unconnected-(IC1-PA1-Pad35)") (class "Default")
      (node (ref "IC1") (pin "35") (pinfunction "PA1_35") (pintype "bidirectional"))
    )
    (net (code "44") (name "unconnected-(IC1-PA2-Pad36)") (class "Default")
      (node (ref "IC1") (pin "36") (pinfunction "PA2_36") (pintype "bidirectional"))
    )
    (net (code "45") (name "unconnected-(IC1-PA3-Pad37)") (class "Default")
      (node (ref "IC1") (pin "37") (pinfunction "PA3_37") (pintype "bidirectional"))
    )
    (net (code "46") (name "unconnected-(IC1-PA4-Pad40)") (class "Default")
      (node (ref "IC1") (pin "40") (pinfunction "PA4_40") (pintype "bidirectional"))
    )
    (net (code "47") (name "unconnected-(IC1-PA5-Pad41)") (class "Default")
      (node (ref "IC1") (pin "41") (pinfunction "PA5_41") (pintype "bidirectional"))
    )
    (net (code "48") (name "unconnected-(IC1-PA6-Pad42)") (class "Default")
      (node (ref "IC1") (pin "42") (pinfunction "PA6_42") (pintype "bidirectional"))
    )
    (net (code "49") (name "unconnected-(IC1-PA7-Pad43)") (class "Default")
      (node (ref "IC1") (pin "43") (pinfunction "PA7_43") (pintype "bidirectional"))
    )
    (net (code "50") (name "unconnected-(IC1-PA8-Pad100)") (class "Default")
      (node (ref "IC1") (pin "100") (pinfunction "PA8_100") (pintype "bidirectional"))
    )
    (net (code "51") (name "unconnected-(IC1-PA9-Pad101)") (class "Default")
      (node (ref "IC1") (pin "101") (pinfunction "PA9_101") (pintype "bidirectional"))
    )
    (net (code "52") (name "unconnected-(IC1-PA10-Pad102)") (class "Default")
      (node (ref "IC1") (pin "102") (pinfunction "PA10_102") (pintype "bidirectional"))
    )
    (net (code "53") (name "unconnected-(IC1-PA11-Pad103)") (class "Default")
      (node (ref "IC1") (pin "103") (pinfunction "PA11_103") (pintype "bidirectional"))
    )
    (net (code "54") (name "unconnected-(IC1-PA12-Pad104)") (class "Default")
      (node (ref "IC1") (pin "104") (pinfunction "PA12_104") (pintype "bidirectional"))
    )
    (net (code "55") (name "unconnected-(IC1-PA15-Pad110)") (class "Default")
      (node (ref "IC1") (pin "110") (pinfunction "PA15_110") (pintype "bidirectional"))
    )
    (net (code "56") (name "unconnected-(IC1-PAO-Pad34)") (class "Default")
      (node (ref "IC1") (pin "34") (pinfunction "PAO_34") (pintype "bidirectional"))
    )
    (net (code "57") (name "unconnected-(IC1-PB4-Pad134)") (class "Default")
      (node (ref "IC1") (pin "134") (pinfunction "PB4_134") (pintype "bidirectional"))
    )
    (net (code "58") (name "unconnected-(IC1-PB5-Pad135)") (class "Default")
      (node (ref "IC1") (pin "135") (pinfunction "PB5_135") (pintype "bidirectional"))
    )
    (net (code "59") (name "unconnected-(IC1-PB6-Pad136)") (class "Default")
      (node (ref "IC1") (pin "136") (pinfunction "PB6_136") (pintype "bidirectional"))
    )
    (net (code "60") (name "unconnected-(IC1-PB7-Pad137)") (class "Default")
      (node (ref "IC1") (pin "137") (pinfunction "PB7_137") (pintype "bidirectional"))
    )
    (net (code "61") (name "unconnected-(IC1-PB8-Pad139)") (class "Default")
      (node (ref "IC1") (pin "139") (pinfunction "PB8_139") (pintype "bidirectional"))
    )
    (net (code "62") (name "unconnected-(IC1-PB9-Pad140)") (class "Default")
      (node (ref "IC1") (pin "140") (pinfunction "PB9_140") (pintype "bidirectional"))
    )
    (net (code "63") (name "unconnected-(IC1-PB10-Pad69)") (class "Default")
      (node (ref "IC1") (pin "69") (pinfunction "PB10_69") (pintype "bidirectional"))
    )
    (net (code "64") (name "unconnected-(IC1-PB11-Pad70)") (class "Default")
      (node (ref "IC1") (pin "70") (pinfunction "PB11_70") (pintype "bidirectional"))
    )
    (net (code "65") (name "unconnected-(IC1-PB12-Pad73)") (class "Default")
      (node (ref "IC1") (pin "73") (pinfunction "PB12_73") (pintype "bidirectional"))
    )
    (net (code "66") (name "unconnected-(IC1-PB13-Pad74)") (class "Default")
      (node (ref "IC1") (pin "74") (pinfunction "PB13_74") (pintype "bidirectional"))
    )
    (net (code "67") (name "unconnected-(IC1-PB14-Pad75)") (class "Default")
      (node (ref "IC1") (pin "75") (pinfunction "PB14_75") (pintype "bidirectional"))
    )
    (net (code "68") (name "unconnected-(IC1-PB15-Pad76)") (class "Default")
      (node (ref "IC1") (pin "76") (pinfunction "PB15_76") (pintype "bidirectional"))
    )
    (net (code "69") (name "unconnected-(IC1-PBO-Pad46)") (class "Default")
      (node (ref "IC1") (pin "46") (pinfunction "PBO_46") (pintype "bidirectional"))
    )
    (net (code "70") (name "unconnected-(IC1-PC1-Pad27)") (class "Default")
      (node (ref "IC1") (pin "27") (pinfunction "PC1_27") (pintype "bidirectional"))
    )
    (net (code "71") (name "unconnected-(IC1-PC2-Pad28)") (class "Default")
      (node (ref "IC1") (pin "28") (pinfunction "PC2_28") (pintype "bidirectional"))
    )
    (net (code "72") (name "unconnected-(IC1-PC3-Pad29)") (class "Default")
      (node (ref "IC1") (pin "29") (pinfunction "PC3_29") (pintype "bidirectional"))
    )
    (net (code "73") (name "unconnected-(IC1-PC4-Pad44)") (class "Default")
      (node (ref "IC1") (pin "44") (pinfunction "PC4_44") (pintype "bidirectional"))
    )
    (net (code "74") (name "unconnected-(IC1-PC5-Pad45)") (class "Default")
      (node (ref "IC1") (pin "45") (pinfunction "PC5_45") (pintype "bidirectional"))
    )
    (net (code "75") (name "unconnected-(IC1-PC6-Pad96)") (class "Default")
      (node (ref "IC1") (pin "96") (pinfunction "PC6_96") (pintype "bidirectional"))
    )
    (net (code "76") (name "unconnected-(IC1-PC7-Pad97)") (class "Default")
      (node (ref "IC1") (pin "97") (pinfunction "PC7_97") (pintype "bidirectional"))
    )
    (net (code "77") (name "unconnected-(IC1-PC8-Pad98)") (class "Default")
      (node (ref "IC1") (pin "98") (pinfunction "PC8_98") (pintype "bidirectional"))
    )
    (net (code "78") (name "unconnected-(IC1-PC9-Pad99)") (class "Default")
      (node (ref "IC1") (pin "99") (pinfunction "PC9_99") (pintype "bidirectional"))
    )
    (net (code "79") (name "unconnected-(IC1-PC10-Pad111)") (class "Default")
      (node (ref "IC1") (pin "111") (pinfunction "PC10_111") (pintype "bidirectional"))
    )
    (net (code "80") (name "unconnected-(IC1-PC13-Pad7)") (class "Default")
      (node (ref "IC1") (pin "7") (pinfunction "PC13_7") (pintype "bidirectional"))
    )
    (net (code "81") (name "unconnected-(IC1-PCO-Pad26)") (class "Default")
      (node (ref "IC1") (pin "26") (pinfunction "PCO_26") (pintype "bidirectional"))
    )
    (net (code "82") (name "unconnected-(IC1-PD1-Pad115)") (class "Default")
      (node (ref "IC1") (pin "115") (pinfunction "PD1_115") (pintype "bidirectional"))
    )
    (net (code "83") (name "unconnected-(IC1-PD3-Pad117)") (class "Default")
      (node (ref "IC1") (pin "117") (pinfunction "PD3_117") (pintype "bidirectional"))
    )
    (net (code "84") (name "unconnected-(IC1-PD4-Pad118)") (class "Default")
      (node (ref "IC1") (pin "118") (pinfunction "PD4_118") (pintype "bidirectional"))
    )
    (net (code "85") (name "unconnected-(IC1-PD5-Pad119)") (class "Default")
      (node (ref "IC1") (pin "119") (pinfunction "PD5_119") (pintype "bidirectional"))
    )
    (net (code "86") (name "unconnected-(IC1-PD6-Pad122)") (class "Default")
      (node (ref "IC1") (pin "122") (pinfunction "PD6_122") (pintype "bidirectional"))
    )
    (net (code "87") (name "unconnected-(IC1-PD7-Pad123)") (class "Default")
      (node (ref "IC1") (pin "123") (pinfunction "PD7_123") (pintype "bidirectional"))
    )
    (net (code "88") (name "unconnected-(IC1-PD8-Pad77)") (class "Default")
      (node (ref "IC1") (pin "77") (pinfunction "PD8_77") (pintype "bidirectional"))
    )
    (net (code "89") (name "unconnected-(IC1-PD9-Pad78)") (class "Default")
      (node (ref "IC1") (pin "78") (pinfunction "PD9_78") (pintype "bidirectional"))
    )
    (net (code "90") (name "unconnected-(IC1-PD10-Pad79)") (class "Default")
      (node (ref "IC1") (pin "79") (pinfunction "PD10_79") (pintype "bidirectional"))
    )
    (net (code "91") (name "unconnected-(IC1-PD11-Pad80)") (class "Default")
      (node (ref "IC1") (pin "80") (pinfunction "PD11_80") (pintype "bidirectional"))
    )
    (net (code "92") (name "unconnected-(IC1-PD12-Pad81)") (class "Default")
      (node (ref "IC1") (pin "81") (pinfunction "PD12_81") (pintype "bidirectional"))
    )
    (net (code "93") (name "unconnected-(IC1-PD13-Pad82)") (class "Default")
      (node (ref "IC1") (pin "82") (pinfunction "PD13_82") (pintype "bidirectional"))
    )
    (net (code "94") (name "unconnected-(IC1-PD14-Pad85)") (class "Default")
      (node (ref "IC1") (pin "85") (pinfunction "PD14_85") (pintype "bidirectional"))
    )
    (net (code "95") (name "unconnected-(IC1-PD15-Pad86)") (class "Default")
      (node (ref "IC1") (pin "86") (pinfunction "PD15_86") (pintype "bidirectional"))
    )
    (net (code "96") (name "unconnected-(IC1-PDO-Pad114)") (class "Default")
      (node (ref "IC1") (pin "114") (pinfunction "PDO_114") (pintype "bidirectional"))
    )
    (net (code "97") (name "unconnected-(IC1-PDR_ON-Pad143)") (class "Default")
      (node (ref "IC1") (pin "143") (pinfunction "PDR_ON_143") (pintype "bidirectional"))
    )
    (net (code "98") (name "unconnected-(IC1-PE1-Pad142)") (class "Default")
      (node (ref "IC1") (pin "142") (pinfunction "PE1_142") (pintype "bidirectional"))
    )
    (net (code "99") (name "unconnected-(IC1-PE2-Pad1)") (class "Default")
      (node (ref "IC1") (pin "1") (pinfunction "PE2_1") (pintype "bidirectional"))
    )
    (net (code "100") (name "unconnected-(IC1-PE3-Pad2)") (class "Default")
      (node (ref "IC1") (pin "2") (pinfunction "PE3_2") (pintype "bidirectional"))
    )
    (net (code "101") (name "unconnected-(IC1-PE4-Pad3)") (class "Default")
      (node (ref "IC1") (pin "3") (pinfunction "PE4_3") (pintype "bidirectional"))
    )
    (net (code "102") (name "unconnected-(IC1-PE5-Pad4)") (class "Default")
      (node (ref "IC1") (pin "4") (pinfunction "PE5_4") (pintype "bidirectional"))
    )
    (net (code "103") (name "unconnected-(IC1-PE11-Pad64)") (class "Default")
      (node (ref "IC1") (pin "64") (pinfunction "PE11_64") (pintype "bidirectional"))
    )
    (net (code "104") (name "unconnected-(IC1-PE12-Pad65)") (class "Default")
      (node (ref "IC1") (pin "65") (pinfunction "PE12_65") (pintype "bidirectional"))
    )
    (net (code "105") (name "unconnected-(IC1-PE13-Pad66)") (class "Default")
      (node (ref "IC1") (pin "66") (pinfunction "PE13_66") (pintype "bidirectional"))
    )
    (net (code "106") (name "unconnected-(IC1-PE14-Pad67)") (class "Default")
      (node (ref "IC1") (pin "67") (pinfunction "PE14_67") (pintype "bidirectional"))
    )
    (net (code "107") (name "unconnected-(IC1-PE15-Pad68)") (class "Default")
      (node (ref "IC1") (pin "68") (pinfunction "PE15_68") (pintype "bidirectional"))
    )
    (net (code "108") (name "unconnected-(IC1-PEO-Pad141)") (class "Default")
      (node (ref "IC1") (pin "141") (pinfunction "PEO_141") (pintype "bidirectional"))
    )
    (net (code "109") (name "unconnected-(IC1-PF1-Pad11)") (class "Default")
      (node (ref "IC1") (pin "11") (pinfunction "PF1_11") (pintype "bidirectional"))
    )
    (net (code "110") (name "unconnected-(IC1-PF2-Pad12)") (class "Default")
      (node (ref "IC1") (pin "12") (pinfunction "PF2_12") (pintype "bidirectional"))
    )
    (net (code "111") (name "unconnected-(IC1-PF3-Pad13)") (class "Default")
      (node (ref "IC1") (pin "13") (pinfunction "PF3_13") (pintype "bidirectional"))
    )
    (net (code "112") (name "unconnected-(IC1-PF4-Pad14)") (class "Default")
      (node (ref "IC1") (pin "14") (pinfunction "PF4_14") (pintype "bidirectional"))
    )
    (net (code "113") (name "unconnected-(IC1-PF5-Pad15)") (class "Default")
      (node (ref "IC1") (pin "15") (pinfunction "PF5_15") (pintype "bidirectional"))
    )
    (net (code "114") (name "unconnected-(IC1-PF7-Pad19)") (class "Default")
      (node (ref "IC1") (pin "19") (pinfunction "PF7_19") (pintype "bidirectional"))
    )
    (net (code "115") (name "unconnected-(IC1-PF8-Pad20)") (class "Default")
      (node (ref "IC1") (pin "20") (pinfunction "PF8_20") (pintype "bidirectional"))
    )
    (net (code "116") (name "unconnected-(IC1-PF9-Pad21)") (class "Default")
      (node (ref "IC1") (pin "21") (pinfunction "PF9_21") (pintype "bidirectional"))
    )
    (net (code "117") (name "unconnected-(IC1-PF10-Pad22)") (class "Default")
      (node (ref "IC1") (pin "22") (pinfunction "PF10_22") (pintype "bidirectional"))
    )
    (net (code "118") (name "unconnected-(IC1-PF11-Pad49)") (class "Default")
      (node (ref "IC1") (pin "49") (pinfunction "PF11_49") (pintype "bidirectional"))
    )
    (net (code "119") (name "unconnected-(IC1-PF12-Pad50)") (class "Default")
      (node (ref "IC1") (pin "50") (pinfunction "PF12_50") (pintype "bidirectional"))
    )
    (net (code "120") (name "unconnected-(IC1-PF13-Pad53)") (class "Default")
      (node (ref "IC1") (pin "53") (pinfunction "PF13_53") (pintype "bidirectional"))
    )
    (net (code "121") (name "unconnected-(IC1-PF14-Pad54)") (class "Default")
      (node (ref "IC1") (pin "54") (pinfunction "PF14_54") (pintype "bidirectional"))
    )
    (net (code "122") (name "unconnected-(IC1-PF15-Pad55)") (class "Default")
      (node (ref "IC1") (pin "55") (pinfunction "PF15_55") (pintype "bidirectional"))
    )
    (net (code "123") (name "unconnected-(IC1-PFO-Pad10)") (class "Default")
      (node (ref "IC1") (pin "10") (pinfunction "PFO_10") (pintype "bidirectional"))
    )
    (net (code "124") (name "unconnected-(IC1-PG1-Pad57)") (class "Default")
      (node (ref "IC1") (pin "57") (pinfunction "PG1_57") (pintype "bidirectional"))
    )
    (net (code "125") (name "unconnected-(IC1-PG2-Pad87)") (class "Default")
      (node (ref "IC1") (pin "87") (pinfunction "PG2_87") (pintype "bidirectional"))
    )
    (net (code "126") (name "unconnected-(IC1-PG3-Pad88)") (class "Default")
      (node (ref "IC1") (pin "88") (pinfunction "PG3_88") (pintype "bidirectional"))
    )
    (net (code "127") (name "unconnected-(IC1-PG4-Pad89)") (class "Default")
      (node (ref "IC1") (pin "89") (pinfunction "PG4_89") (pintype "bidirectional"))
    )
    (net (code "128") (name "unconnected-(IC1-PG5-Pad90)") (class "Default")
      (node (ref "IC1") (pin "90") (pinfunction "PG5_90") (pintype "bidirectional"))
    )
    (net (code "129") (name "unconnected-(IC1-PG6-Pad91)") (class "Default")
      (node (ref "IC1") (pin "91") (pinfunction "PG6_91") (pintype "bidirectional"))
    )
    (net (code "130") (name "unconnected-(IC1-PG7-Pad92)") (class "Default")
      (node (ref "IC1") (pin "92") (pinfunction "PG7_92") (pintype "bidirectional"))
    )
    (net (code "131") (name "unconnected-(IC1-PG8-Pad93)") (class "Default")
      (node (ref "IC1") (pin "93") (pinfunction "PG8_93") (pintype "bidirectional"))
    )
    (net (code "132") (name "unconnected-(IC1-PG9-Pad124)") (class "Default")
      (node (ref "IC1") (pin "124") (pinfunction "PG9_124") (pintype "bidirectional"))
    )
    (net (code "133") (name "unconnected-(IC1-PG10-Pad125)") (class "Default")
      (node (ref "IC1") (pin "125") (pinfunction "PG10_125") (pintype "bidirectional"))
    )
    (net (code "134") (name "unconnected-(IC1-PG11-Pad126)") (class "Default")
      (node (ref "IC1") (pin "126") (pinfunction "PG11_126") (pintype "bidirectional"))
    )
    (net (code "135") (name "unconnected-(IC1-PG12-Pad127)") (class "Default")
      (node (ref "IC1") (pin "127") (pinfunction "PG12_127") (pintype "bidirectional"))
    )
    (net (code "136") (name "unconnected-(IC1-PG13-Pad128)") (class "Default")
      (node (ref "IC1") (pin "128") (pinfunction "PG13_128") (pintype "bidirectional"))
    )
    (net (code "137") (name "unconnected-(IC1-PG14-Pad129)") (class "Default")
      (node (ref "IC1") (pin "129") (pinfunction "PG14_129") (pintype "bidirectional"))
    )
    (net (code "138") (name "unconnected-(IC1-PG15-Pad132)") (class "Default")
      (node (ref "IC1") (pin "132") (pinfunction "PG15_132") (pintype "bidirectional"))
    )
    (net (code "139") (name "unconnected-(IC1-PGO-Pad56)") (class "Default")
      (node (ref "IC1") (pin "56") (pinfunction "PGO_56") (pintype "bidirectional"))
    )
    (net (code "140") (name "unconnected-(IC1-VBAT-Pad6)") (class "Default")
      (node (ref "IC1") (pin "6") (pinfunction "VBAT_6") (pintype "bidirectional"))
    )
    (net (code "141") (name "unconnected-(J2-NC{slash}TDI-Pad8)") (class "Default")
      (node (ref "J2") (pin "8") (pinfunction "NC/TDI_8") (pintype "bidirectional"))
    )
    (net (code "142") (name "unconnected-(J3A-S-Pad1)") (class "Default")
      (node (ref "J3") (pin "1") (pinfunction "S_1") (pintype "passive"))
    )
    (net (code "143") (name "unconnected-(P1-Pad2)") (class "Default")
      (node (ref "P1") (pin "2") (pinfunction "2_2") (pintype "passive"))
    )
    (net (code "144") (name "unconnected-(P1-Pad3)") (class "Default")
      (node (ref "P1") (pin "3") (pinfunction "3_3") (pintype "passive"))
    )
    (net (code "145") (name "unconnected-(P1-Pad4)") (class "Default")
      (node (ref "P1") (pin "4") (pinfunction "4_4") (pintype "passive"))
    )
    (net (code "146") (name "unconnected-(P1-Pad5)") (class "Default")
      (node (ref "P1") (pin "5") (pinfunction "5_5") (pintype "passive"))
    )
    (net (code "147") (name "unconnected-(P1-Pad6)") (class "Default")
      (node (ref "P1") (pin "6") (pinfunction "6_6") (pintype "passive"))
    )
    (net (code "148") (name "unconnected-(P1-Pad9)") (class "Default")
      (node (ref "P1") (pin "9") (pinfunction "9_9") (pintype "passive"))
    )
    (net (code "149") (name "unconnected-(P1-Pad10)") (class "Default")
      (node (ref "P1") (pin "10") (pinfunction "10_10") (pintype "passive"))
    )
    (net (code "150") (name "unconnected-(P1-Pad11)") (class "Default")
      (node (ref "P1") (pin "11") (pinfunction "11_11") (pintype "passive"))
    )
    (net (code "151") (name "unconnected-(P1-Pad12)") (class "Default")
      (node (ref "P1") (pin "12") (pinfunction "12_12") (pintype "passive"))
    )
    (net (code "152") (name "unconnected-(P1-Pad15)") (class "Default")
      (node (ref "P1") (pin "15") (pinfunction "15_15") (pintype "passive"))
    )
    (net (code "153") (name "unconnected-(P1-Pad16)") (class "Default")
      (node (ref "P1") (pin "16") (pinfunction "16_16") (pintype "passive"))
    )
    (net (code "154") (name "unconnected-(P1-Pad17)") (class "Default")
      (node (ref "P1") (pin "17") (pinfunction "17_17") (pintype "passive"))
    )
    (net (code "155") (name "unconnected-(P1-Pad18)") (class "Default")
      (node (ref "P1") (pin "18") (pinfunction "18_18") (pintype "passive"))
    )
    (net (code "156") (name "unconnected-(P1-Pad21)") (class "Default")
      (node (ref "P1") (pin "21") (pinfunction "21_21") (pintype "passive"))
    )
    (net (code "157") (name "unconnected-(P1-Pad22)") (class "Default")
      (node (ref "P1") (pin "22") (pinfunction "22_22") (pintype "passive"))
    )
    (net (code "158") (name "unconnected-(P1-Pad23)") (class "Default")
      (node (ref "P1") (pin "23") (pinfunction "23_23") (pintype "passive"))
    )
    (net (code "159") (name "unconnected-(P1-Pad24)") (class "Default")
      (node (ref "P1") (pin "24") (pinfunction "24_24") (pintype "passive"))
    )
    (net (code "160") (name "unconnected-(P1-Pad27)") (class "Default")
      (node (ref "P1") (pin "27") (pinfunction "27_27") (pintype "passive"))
    )
    (net (code "161") (name "unconnected-(P1-Pad28)") (class "Default")
      (node (ref "P1") (pin "28") (pinfunction "28_28") (pintype "passive"))
    )
    (net (code "162") (name "unconnected-(P1-Pad29)") (class "Default")
      (node (ref "P1") (pin "29") (pinfunction "29_29") (pintype "passive"))
    )
    (net (code "163") (name "unconnected-(P1-Pad30)") (class "Default")
      (node (ref "P1") (pin "30") (pinfunction "30_30") (pintype "passive"))
    )
    (net (code "164") (name "unconnected-(P1-Pad33)") (class "Default")
      (node (ref "P1") (pin "33") (pinfunction "33_33") (pintype "passive"))
    )
    (net (code "165") (name "unconnected-(P1-Pad34)") (class "Default")
      (node (ref "P1") (pin "34") (pinfunction "34_34") (pintype "passive"))
    )
    (net (code "166") (name "unconnected-(P1-Pad35)") (class "Default")
      (node (ref "P1") (pin "35") (pinfunction "35_35") (pintype "passive"))
    )
    (net (code "167") (name "unconnected-(P1-Pad36)") (class "Default")
      (node (ref "P1") (pin "36") (pinfunction "36_36") (pintype "passive"))
    )
    (net (code "168") (name "unconnected-(P1-Pad39)") (class "Default")
      (node (ref "P1") (pin "39") (pinfunction "39_39") (pintype "passive"))
    )
    (net (code "169") (name "unconnected-(P1-Pad40)") (class "Default")
      (node (ref "P1") (pin "40") (pinfunction "40_40") (pintype "passive"))
    )
    (net (code "170") (name "unconnected-(P1-Pad41)") (class "Default")
      (node (ref "P1") (pin "41") (pinfunction "41_41") (pintype "passive"))
    )
    (net (code "171") (name "unconnected-(P1-Pad42)") (class "Default")
      (node (ref "P1") (pin "42") (pinfunction "42_42") (pintype "passive"))
    )
    (net (code "172") (name "unconnected-(P1-Pad45)") (class "Default")
      (node (ref "P1") (pin "45") (pinfunction "45_45") (pintype "passive"))
    )
    (net (code "173") (name "unconnected-(P1-Pad46)") (class "Default")
      (node (ref "P1") (pin "46") (pinfunction "46_46") (pintype "passive"))
    )
    (net (code "174") (name "unconnected-(P1-Pad47)") (class "Default")
      (node (ref "P1") (pin "47") (pinfunction "47_47") (pintype "passive"))
    )
    (net (code "175") (name "unconnected-(P1-Pad48)") (class "Default")
      (node (ref "P1") (pin "48") (pinfunction "48_48") (pintype "passive"))
    )
    (net (code "176") (name "unconnected-(P1-Pad52)") (class "Default")
      (node (ref "P1") (pin "52") (pinfunction "52_52") (pintype "passive"))
    )
    (net (code "177") (name "unconnected-(P1-Pad54)") (class "Default")
      (node (ref "P1") (pin "54") (pinfunction "54_54") (pintype "passive"))
    )
    (net (code "178") (name "unconnected-(P1-Pad57)") (class "Default")
      (node (ref "P1") (pin "57") (pinfunction "57_57") (pintype "passive"))
    )
    (net (code "179") (name "unconnected-(P1-Pad58)") (class "Default")
      (node (ref "P1") (pin "58") (pinfunction "58_58") (pintype "passive"))
    )
    (net (code "180") (name "unconnected-(P1-Pad59)") (class "Default")
      (node (ref "P1") (pin "59") (pinfunction "59_59") (pintype "passive"))
    )
    (net (code "181") (name "unconnected-(P1-Pad60)") (class "Default")
      (node (ref "P1") (pin "60") (pinfunction "60_60") (pintype "passive"))
    )
    (net (code "182") (name "unconnected-(P1-Pad63)") (class "Default")
      (node (ref "P1") (pin "63") (pinfunction "63_63") (pintype "passive"))
    )
    (net (code "183") (name "unconnected-(P1-Pad64)") (class "Default")
      (node (ref "P1") (pin "64") (pinfunction "64_64") (pintype "passive"))
    )
    (net (code "184") (name "unconnected-(P1-Pad65)") (class "Default")
      (node (ref "P1") (pin "65") (pinfunction "65_65") (pintype "passive"))
    )
    (net (code "185") (name "unconnected-(P1-Pad66)") (class "Default")
      (node (ref "P1") (pin "66") (pinfunction "66_66") (pintype "passive"))
    )
    (net (code "186") (name "unconnected-(P1-Pad69)") (class "Default")
      (node (ref "P1") (pin "69") (pinfunction "69_69") (pintype "passive"))
    )
    (net (code "187") (name "unconnected-(P1-Pad70)") (class "Default")
      (node (ref "P1") (pin "70") (pinfunction "70_70") (pintype "passive"))
    )
    (net (code "188") (name "unconnected-(P1-Pad71)") (class "Default")
      (node (ref "P1") (pin "71") (pinfunction "71_71") (pintype "passive"))
    )
    (net (code "189") (name "unconnected-(P1-Pad72)") (class "Default")
      (node (ref "P1") (pin "72") (pinfunction "72_72") (pintype "passive"))
    )
    (net (code "190") (name "unconnected-(P1-Pad75)") (class "Default")
      (node (ref "P1") (pin "75") (pinfunction "75_75") (pintype "passive"))
    )
    (net (code "191") (name "unconnected-(P1-Pad76)") (class "Default")
      (node (ref "P1") (pin "76") (pinfunction "76_76") (pintype "passive"))
    )
    (net (code "192") (name "unconnected-(P1-Pad77)") (class "Default")
      (node (ref "P1") (pin "77") (pinfunction "77_77") (pintype "passive"))
    )
    (net (code "193") (name "unconnected-(P1-Pad78)") (class "Default")
      (node (ref "P1") (pin "78") (pinfunction "78_78") (pintype "passive"))
    )
    (net (code "194") (name "unconnected-(P1-Pad81)") (class "Default")
      (node (ref "P1") (pin "81") (pinfunction "81_81") (pintype "passive"))
    )
    (net (code "195") (name "unconnected-(P1-Pad82)") (class "Default")
      (node (ref "P1") (pin "82") (pinfunction "82_82") (pintype "passive"))
    )
    (net (code "196") (name "unconnected-(P1-Pad83)") (class "Default")
      (node (ref "P1") (pin "83") (pinfunction "83_83") (pintype "passive"))
    )
    (net (code "197") (name "unconnected-(P1-Pad84)") (class "Default")
      (node (ref "P1") (pin "84") (pinfunction "84_84") (pintype "passive"))
    )
    (net (code "198") (name "unconnected-(P1-Pad87)") (class "Default")
      (node (ref "P1") (pin "87") (pinfunction "87_87") (pintype "passive"))
    )
    (net (code "199") (name "unconnected-(P1-Pad88)") (class "Default")
      (node (ref "P1") (pin "88") (pinfunction "88_88") (pintype "passive"))
    )
    (net (code "200") (name "unconnected-(P1-Pad89)") (class "Default")
      (node (ref "P1") (pin "89") (pinfunction "89_89") (pintype "passive"))
    )
    (net (code "201") (name "unconnected-(P1-Pad90)") (class "Default")
      (node (ref "P1") (pin "90") (pinfunction "90_90") (pintype "passive"))
    )
    (net (code "202") (name "unconnected-(P1-Pad93)") (class "Default")
      (node (ref "P1") (pin "93") (pinfunction "93_93") (pintype "passive"))
    )
    (net (code "203") (name "unconnected-(P1-Pad94)") (class "Default")
      (node (ref "P1") (pin "94") (pinfunction "94_94") (pintype "passive"))
    )
    (net (code "204") (name "unconnected-(P1-Pad95)") (class "Default")
      (node (ref "P1") (pin "95") (pinfunction "95_95") (pintype "passive"))
    )
    (net (code "205") (name "unconnected-(P1-Pad96)") (class "Default")
      (node (ref "P1") (pin "96") (pinfunction "96_96") (pintype "passive"))
    )
    (net (code "206") (name "unconnected-(P1-Pad99)") (class "Default")
      (node (ref "P1") (pin "99") (pinfunction "99_99") (pintype "passive"))
    )
    (net (code "207") (name "unconnected-(P1-Pad100)") (class "Default")
      (node (ref "P1") (pin "100") (pinfunction "100_100") (pintype "passive"))
    )
    (net (code "208") (name "unconnected-(P1-Pad101)") (class "Default")
      (node (ref "P1") (pin "101") (pinfunction "101_101") (pintype "passive"))
    )
    (net (code "209") (name "unconnected-(P1-Pad102)") (class "Default")
      (node (ref "P1") (pin "102") (pinfunction "102_102") (pintype "passive"))
    )
    (net (code "210") (name "unconnected-(P1-Pad105)") (class "Default")
      (node (ref "P1") (pin "105") (pinfunction "105_105") (pintype "passive"))
    )
    (net (code "211") (name "unconnected-(P1-Pad106)") (class "Default")
      (node (ref "P1") (pin "106") (pinfunction "106_106") (pintype "passive"))
    )
    (net (code "212") (name "unconnected-(P1-Pad107)") (class "Default")
      (node (ref "P1") (pin "107") (pinfunction "107_107") (pintype "passive"))
    )
    (net (code "213") (name "unconnected-(P1-Pad108)") (class "Default")
      (node (ref "P1") (pin "108") (pinfunction "108_108") (pintype "passive"))
    )
    (net (code "214") (name "unconnected-(P1-Pad111)") (class "Default")
      (node (ref "P1") (pin "111") (pinfunction "111_111") (pintype "passive"))
    )
    (net (code "215") (name "unconnected-(P1-Pad112)") (class "Default")
      (node (ref "P1") (pin "112") (pinfunction "112_112") (pintype "passive"))
    )
    (net (code "216") (name "unconnected-(P1-Pad113)") (class "Default")
      (node (ref "P1") (pin "113") (pinfunction "113_113") (pintype "passive"))
    )
    (net (code "217") (name "unconnected-(P1-Pad114)") (class "Default")
      (node (ref "P1") (pin "114") (pinfunction "114_114") (pintype "passive"))
    )
    (net (code "218") (name "unconnected-(P1-Pad117)") (class "Default")
      (node (ref "P1") (pin "117") (pinfunction "117_117") (pintype "passive"))
    )
    (net (code "219") (name "unconnected-(P1-Pad118)") (class "Default")
      (node (ref "P1") (pin "118") (pinfunction "118_118") (pintype "passive"))
    )
    (net (code "220") (name "unconnected-(P1-Pad119)") (class "Default")
      (node (ref "P1") (pin "119") (pinfunction "119_119") (pintype "passive"))
    )
    (net (code "221") (name "unconnected-(P1-Pad120)") (class "Default")
      (node (ref "P1") (pin "120") (pinfunction "120_120") (pintype "passive"))
    )
    (net (code "222") (name "unconnected-(P1-Pad123)") (class "Default")
      (node (ref "P1") (pin "123") (pinfunction "123_123") (pintype "passive"))
    )
    (net (code "223") (name "unconnected-(P1-Pad124)") (class "Default")
      (node (ref "P1") (pin "124") (pinfunction "124_124") (pintype "passive"))
    )
    (net (code "224") (name "unconnected-(P1-Pad125)") (class "Default")
      (node (ref "P1") (pin "125") (pinfunction "125_125") (pintype "passive"))
    )
    (net (code "225") (name "unconnected-(P1-Pad126)") (class "Default")
      (node (ref "P1") (pin "126") (pinfunction "126_126") (pintype "passive"))
    )
    (net (code "226") (name "unconnected-(P1-Pad128)") (class "Default")
      (node (ref "P1") (pin "128") (pinfunction "128_128") (pintype "passive"))
    )
    (net (code "227") (name "unconnected-(P1-Pad129)") (class "Default")
      (node (ref "P1") (pin "129") (pinfunction "129_129") (pintype "passive"))
    )
    (net (code "228") (name "unconnected-(P1-Pad130)") (class "Default")
      (node (ref "P1") (pin "130") (pinfunction "130_130") (pintype "passive"))
    )
    (net (code "229") (name "unconnected-(P1-Pad131)") (class "Default")
      (node (ref "P1") (pin "131") (pinfunction "131_131") (pintype "passive"))
    )
    (net (code "230") (name "unconnected-(P1-Pad132)") (class "Default")
      (node (ref "P1") (pin "132") (pinfunction "132_132") (pintype "passive"))
    )
    (net (code "231") (name "unconnected-(P1-Pad135)") (class "Default")
      (node (ref "P1") (pin "135") (pinfunction "135_135") (pintype "passive"))
    )
    (net (code "232") (name "unconnected-(P1-Pad136)") (class "Default")
      (node (ref "P1") (pin "136") (pinfunction "136_136") (pintype "passive"))
    )
    (net (code "233") (name "unconnected-(P1-Pad137)") (class "Default")
      (node (ref "P1") (pin "137") (pinfunction "137_137") (pintype "passive"))
    )
    (net (code "234") (name "unconnected-(P1-Pad138)") (class "Default")
      (node (ref "P1") (pin "138") (pinfunction "138_138") (pintype "passive"))
    )
    (net (code "235") (name "unconnected-(P1-Pad141)") (class "Default")
      (node (ref "P1") (pin "141") (pinfunction "141_141") (pintype "passive"))
    )
    (net (code "236") (name "unconnected-(P1-Pad142)") (class "Default")
      (node (ref "P1") (pin "142") (pinfunction "142_142") (pintype "passive"))
    )
    (net (code "237") (name "unconnected-(P1-Pad143)") (class "Default")
      (node (ref "P1") (pin "143") (pinfunction "143_143") (pintype "passive"))
    )
    (net (code "238") (name "unconnected-(P1-Pad144)") (class "Default")
      (node (ref "P1") (pin "144") (pinfunction "144_144") (pintype "passive"))
    )
    (net (code "239") (name "unconnected-(P1-Pad147)") (class "Default")
      (node (ref "P1") (pin "147") (pinfunction "147_147") (pintype "passive"))
    )
    (net (code "240") (name "unconnected-(P1-Pad148)") (class "Default")
      (node (ref "P1") (pin "148") (pinfunction "148_148") (pintype "passive"))
    )
    (net (code "241") (name "unconnected-(P1-Pad149)") (class "Default")
      (node (ref "P1") (pin "149") (pinfunction "149_149") (pintype "passive"))
    )
    (net (code "242") (name "unconnected-(P1-Pad150)") (class "Default")
      (node (ref "P1") (pin "150") (pinfunction "150_150") (pintype "passive"))
    )
    (net (code "243") (name "unconnected-(P1-Pad153)") (class "Default")
      (node (ref "P1") (pin "153") (pinfunction "153_153") (pintype "passive"))
    )
    (net (code "244") (name "unconnected-(P1-Pad154)") (class "Default")
      (node (ref "P1") (pin "154") (pinfunction "154_154") (pintype "passive"))
    )
    (net (code "245") (name "unconnected-(P1-Pad155)") (class "Default")
      (node (ref "P1") (pin "155") (pinfunction "155_155") (pintype "passive"))
    )
    (net (code "246") (name "unconnected-(P1-Pad156)") (class "Default")
      (node (ref "P1") (pin "156") (pinfunction "156_156") (pintype "passive"))
    )
    (net (code "247") (name "unconnected-(P1-Pad158)") (class "Default")
      (node (ref "P1") (pin "158") (pinfunction "158_158") (pintype "passive"))
    )
    (net (code "248") (name "unconnected-(P1-Pad159)") (class "Default")
      (node (ref "P1") (pin "159") (pinfunction "159_159") (pintype "passive"))
    )
    (net (code "249") (name "unconnected-(P1-Pad160)") (class "Default")
      (node (ref "P1") (pin "160") (pinfunction "160_160") (pintype "passive"))
    )
    (net (code "250") (name "unconnected-(P1-Pad161)") (class "Default")
      (node (ref "P1") (pin "161") (pinfunction "161_161") (pintype "passive"))
    )
    (net (code "251") (name "unconnected-(P1-Pad162)") (class "Default")
      (node (ref "P1") (pin "162") (pinfunction "162_162") (pintype "passive"))
    )
    (net (code "252") (name "unconnected-(P1-Pad165)") (class "Default")
      (node (ref "P1") (pin "165") (pinfunction "165_165") (pintype "passive"))
    )
    (net (code "253") (name "unconnected-(P1-Pad166)") (class "Default")
      (node (ref "P1") (pin "166") (pinfunction "166_166") (pintype "passive"))
    )
    (net (code "254") (name "unconnected-(P1-Pad167)") (class "Default")
      (node (ref "P1") (pin "167") (pinfunction "167_167") (pintype "passive"))
    )
    (net (code "255") (name "unconnected-(P1-Pad171)") (class "Default")
      (node (ref "P1") (pin "171") (pinfunction "171_171") (pintype "passive"))
    )
    (net (code "256") (name "unconnected-(P1-Pad172)") (class "Default")
      (node (ref "P1") (pin "172") (pinfunction "172_172") (pintype "passive"))
    )
    (net (code "257") (name "unconnected-(P1-Pad173)") (class "Default")
      (node (ref "P1") (pin "173") (pinfunction "173_173") (pintype "passive"))
    )
    (net (code "258") (name "unconnected-(P1-Pad174)") (class "Default")
      (node (ref "P1") (pin "174") (pinfunction "174_174") (pintype "passive"))
    )
    (net (code "259") (name "unconnected-(P1-Pad175)") (class "Default")
      (node (ref "P1") (pin "175") (pinfunction "175_175") (pintype "passive"))
    )
    (net (code "260") (name "unconnected-(P1-Pad176)") (class "Default")
      (node (ref "P1") (pin "176") (pinfunction "176_176") (pintype "passive"))
    )
    (net (code "261") (name "unconnected-(P1-Pad178)") (class "Default")
      (node (ref "P1") (pin "178") (pinfunction "178_178") (pintype "passive"))
    )
    (net (code "262") (name "unconnected-(P1-Pad179)") (class "Default")
      (node (ref "P1") (pin "179") (pinfunction "179_179") (pintype "passive"))
    )
    (net (code "263") (name "unconnected-(P1-Pad180)") (class "Default")
      (node (ref "P1") (pin "180") (pinfunction "180_180") (pintype "passive"))
    )
    (net (code "264") (name "unconnected-(P1-Pad189)") (class "Default")
      (node (ref "P1") (pin "189") (pinfunction "189_189") (pintype "passive"))
    )
    (net (code "265") (name "unconnected-(P1-Pad190)") (class "Default")
      (node (ref "P1") (pin "190") (pinfunction "190_190") (pintype "passive"))
    )
    (net (code "266") (name "unconnected-(U1B-NC-Pad19)") (class "Default")
      (node (ref "U1") (pin "19") (pinfunction "NC_19") (pintype "passive"))
    )
    (net (code "267") (name "unconnected-(U1B-NC_2-Pad1)") (class "Default")
      (node (ref "U1") (pin "1") (pinfunction "NC_2_1") (pintype "passive"))
    )
    (net (code "268") (name "unconnected-(U1B-NC_3-Pad2)") (class "Default")
      (node (ref "U1") (pin "2") (pinfunction "NC_3_2") (pintype "passive"))
    )
    (net (code "269") (name "unconnected-(U1B-NC_4-Pad3)") (class "Default")
      (node (ref "U1") (pin "3") (pinfunction "NC_4_3") (pintype "passive"))
    )
    (net (code "270") (name "unconnected-(U1B-NC_5-Pad5)") (class "Default")
      (node (ref "U1") (pin "5") (pinfunction "NC_5_5") (pintype "passive"))
    )
    (net (code "271") (name "unconnected-(U1B-NC_6-Pad7)") (class "Default")
      (node (ref "U1") (pin "7") (pinfunction "NC_6_7") (pintype "passive"))
    )
    (net (code "272") (name "unconnected-(U1B-NC_7-Pad9)") (class "Default")
      (node (ref "U1") (pin "9") (pinfunction "NC_7_9") (pintype "passive"))
    )
    (net (code "273") (name "unconnected-(U1B-NC_8-Pad10)") (class "Default")
      (node (ref "U1") (pin "10") (pinfunction "NC_8_10") (pintype "passive"))
    )
    (net (code "274") (name "unconnected-(U1B-NC_9-Pad11)") (class "Default")
      (node (ref "U1") (pin "11") (pinfunction "NC_9_11") (pintype "passive"))
    )
    (net (code "275") (name "unconnected-(U1B-NC_10-Pad12)") (class "Default")
      (node (ref "U1") (pin "12") (pinfunction "NC_10_12") (pintype "passive"))
    )
    (net (code "276") (name "unconnected-(U1B-NC_11-Pad13)") (class "Default")
      (node (ref "U1") (pin "13") (pinfunction "NC_11_13") (pintype "passive"))
    )
    (net (code "277") (name "unconnected-(U1B-NC_12-Pad14)") (class "Default")
      (node (ref "U1") (pin "14") (pinfunction "NC_12_14") (pintype "passive"))
    )
    (net (code "278") (name "unconnected-(U1B-NC_13-Pad15)") (class "Default")
      (node (ref "U1") (pin "15") (pinfunction "NC_13_15") (pintype "passive"))
    )
    (net (code "279") (name "unconnected-(U1B-NC_14-Pad16)") (class "Default")
      (node (ref "U1") (pin "16") (pinfunction "NC_14_16") (pintype "passive"))
    )
    (net (code "280") (name "unconnected-(U1B-NC_15-Pad17)") (class "Default")
      (node (ref "U1") (pin "17") (pinfunction "NC_15_17") (pintype "passive"))
    )
    (net (code "281") (name "unconnected-(U1B-NC_16-Pad18)") (class "Default")
      (node (ref "U1") (pin "18") (pinfunction "NC_16_18") (pintype "passive"))
    )
    (net (code "282") (name "unconnected-(X1B-KL-Pad10)") (class "Default")
      (node (ref "X1") (pin "10") (pinfunction "KL_10") (pintype "passive"))
    )
    (net (code "283") (name "unconnected-(X1E-KL-Pad13)") (class "Default")
      (node (ref "X1") (pin "13") (pinfunction "KL_13") (pintype "passive"))
    )
    (net (code "284") (name "unconnected-(X1F-KL-Pad14)") (class "Default")
      (node (ref "X1") (pin "14") (pinfunction "KL_14") (pintype "passive"))
    )
    (net (code "285") (name "unconnected-(X1G-KL-Pad15)") (class "Default")
      (node (ref "X1") (pin "15") (pinfunction "KL_15") (pintype "passive"))
    )
    (net (code "286") (name "unconnected-(X1H-KL-Pad16)") (class "Default")
      (node (ref "X1") (pin "16") (pinfunction "KL_16") (pintype "passive"))
    )
    (net (code "287") (name "unconnected-(X1R-KL-Pad7)") (class "Default")
      (node (ref "X1") (pin "7") (pinfunction "KL_7") (pintype "passive"))
    )
    (net (code "288") (name "unconnected-(X1T-KL-Pad9)") (class "Default")
      (node (ref "X1") (pin "9") (pinfunction "KL_9") (pintype "passive"))
    )
  )
)
